# Control_Board.net
KiCad netlist of a schematic drawn in EAGLE
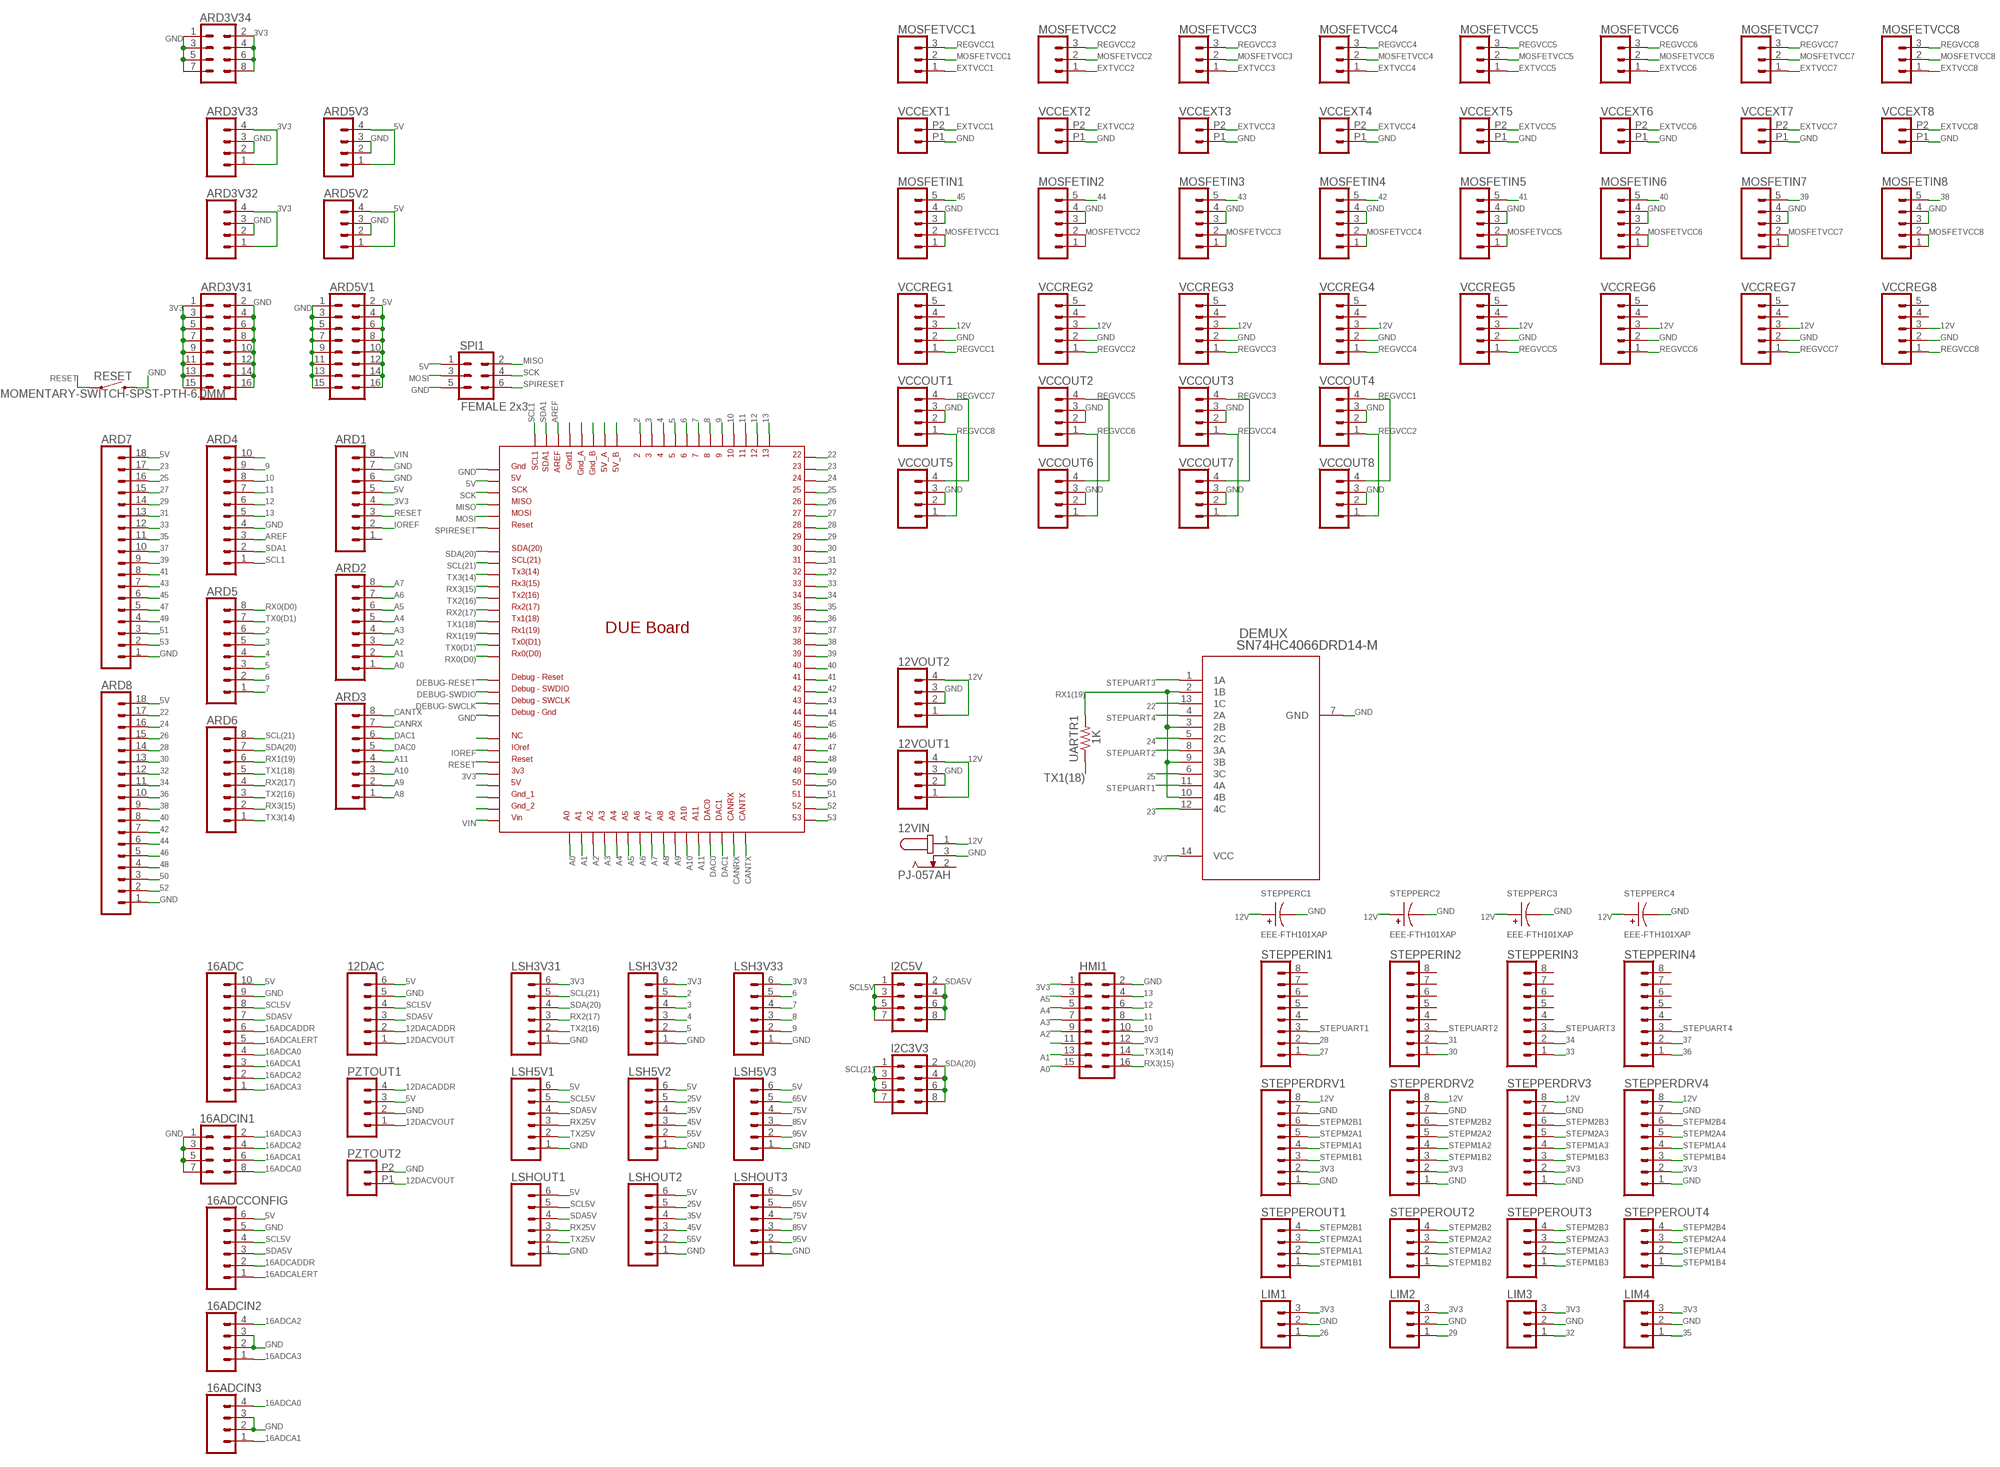
[diagram p0: schematic, sheet 1]

(export (version "E")
  (design (tool "Eeschema 10.0.6"))
  (components
    (comp (ref "12DAC")
      (value "CONN_06LOCK")
      (footprint "eagle-import:1X06_LOCK")
      (libsource (lib "eagle-import") (part "CONN_06LOCK"))
    )
    (comp (ref "12VIN")
      (value "PJ-057AH")
      (footprint "eagle-import:CUI_PJ-057AH")
      (fields (field (name "DIGI-KEY_PART_NUMBER") "CP-057AH-ND") (field (name "MF") "CUI Inc."))
      (libsource (lib "eagle-import") (part "PJ-057AH"))
    )
    (comp (ref "12VOUT1")
      (value "CONN_04POLAR")
      (footprint "eagle-import:MOLEX-1X4")
      (libsource (lib "eagle-import") (part "CONN_04POLAR"))
    )
    (comp (ref "12VOUT2")
      (value "CONN_04POLAR")
      (footprint "eagle-import:MOLEX-1X4")
      (libsource (lib "eagle-import") (part "CONN_04POLAR"))
    )
    (comp (ref "16ADC")
      (value "CONN_10LOCK")
      (footprint "eagle-import:1X10_LOCK")
      (libsource (lib "eagle-import") (part "CONN_10LOCK"))
    )
    (comp (ref "16ADCCONFIG")
      (value "CONN_06LOCK")
      (footprint "eagle-import:1X06_LOCK")
      (libsource (lib "eagle-import") (part "CONN_06LOCK"))
    )
    (comp (ref "16ADCIN1")
      (value "CONN_04X2")
      (footprint "eagle-import:2X4")
      (libsource (lib "eagle-import") (part "CONN_04X2"))
    )
    (comp (ref "16ADCIN2")
      (value "CONN_04POLAR")
      (footprint "eagle-import:MOLEX-1X4")
      (libsource (lib "eagle-import") (part "CONN_04POLAR"))
    )
    (comp (ref "16ADCIN3")
      (value "CONN_04POLAR")
      (footprint "eagle-import:MOLEX-1X4")
      (libsource (lib "eagle-import") (part "CONN_04POLAR"))
    )
    (comp (ref "ARD1")
      (value "CONN_08LOCK")
      (footprint "eagle-import:1X08_LOCK")
      (libsource (lib "eagle-import") (part "CONN_08LOCK"))
    )
    (comp (ref "ARD2")
      (value "CONN_08LOCK")
      (footprint "eagle-import:1X08_LOCK")
      (libsource (lib "eagle-import") (part "CONN_08LOCK"))
    )
    (comp (ref "ARD3")
      (value "CONN_08LOCK")
      (footprint "eagle-import:1X08_LOCK")
      (libsource (lib "eagle-import") (part "CONN_08LOCK"))
    )
    (comp (ref "ARD3V31")
      (value "CONN_08X2")
      (footprint "eagle-import:2X8")
      (libsource (lib "eagle-import") (part "CONN_08X2"))
    )
    (comp (ref "ARD3V32")
      (value "CONN_04POLAR")
      (footprint "eagle-import:MOLEX-1X4")
      (libsource (lib "eagle-import") (part "CONN_04POLAR"))
    )
    (comp (ref "ARD3V33")
      (value "CONN_04POLAR")
      (footprint "eagle-import:MOLEX-1X4")
      (libsource (lib "eagle-import") (part "CONN_04POLAR"))
    )
    (comp (ref "ARD3V34")
      (value "CONN_04X2")
      (footprint "eagle-import:2X4")
      (libsource (lib "eagle-import") (part "CONN_04X2"))
    )
    (comp (ref "ARD4")
      (value "CONN_10LOCK")
      (footprint "eagle-import:1X10_LOCK")
      (libsource (lib "eagle-import") (part "CONN_10LOCK"))
    )
    (comp (ref "ARD5")
      (value "CONN_08LOCK")
      (footprint "eagle-import:1X08_LOCK")
      (libsource (lib "eagle-import") (part "CONN_08LOCK"))
    )
    (comp (ref "ARD5V1")
      (value "CONN_08X2")
      (footprint "eagle-import:2X8")
      (libsource (lib "eagle-import") (part "CONN_08X2"))
    )
    (comp (ref "ARD5V2")
      (value "CONN_04POLAR")
      (footprint "eagle-import:MOLEX-1X4")
      (libsource (lib "eagle-import") (part "CONN_04POLAR"))
    )
    (comp (ref "ARD5V3")
      (value "CONN_04POLAR")
      (footprint "eagle-import:MOLEX-1X4")
      (libsource (lib "eagle-import") (part "CONN_04POLAR"))
    )
    (comp (ref "ARD6")
      (value "CONN_08LOCK")
      (footprint "eagle-import:1X08_LOCK")
      (libsource (lib "eagle-import") (part "CONN_08LOCK"))
    )
    (comp (ref "ARD7")
      (value "CONN_18")
      (footprint "eagle-import:1X18")
      (libsource (lib "eagle-import") (part "CONN_18"))
    )
    (comp (ref "ARD8")
      (value "CONN_18")
      (footprint "eagle-import:1X18")
      (libsource (lib "eagle-import") (part "CONN_18"))
    )
    (comp (ref "DEMUX")
      (value "SN74HC4066DRD14-M")
      (footprint "eagle-import:D14-M")
      (fields (field (name "MANUFACTURER_PART_NUMBER") "SN74HC4066DR"))
      (libsource (lib "eagle-import") (part "SN74HC4066DRD14-M"))
    )
    (comp (ref "HMI1")
      (value "CONN_08X2")
      (footprint "eagle-import:2X8")
      (libsource (lib "eagle-import") (part "CONN_08X2"))
    )
    (comp (ref "I2C3V3")
      (value "CONN_04X2")
      (footprint "eagle-import:2X4")
      (libsource (lib "eagle-import") (part "CONN_04X2"))
    )
    (comp (ref "I2C5V")
      (value "CONN_04X2")
      (footprint "eagle-import:2X4")
      (libsource (lib "eagle-import") (part "CONN_04X2"))
    )
    (comp (ref "LIM1")
      (value "CONN_03LOCK")
      (footprint "eagle-import:1X03_LOCK")
      (libsource (lib "eagle-import") (part "CONN_03LOCK"))
    )
    (comp (ref "LIM2")
      (value "CONN_03LOCK")
      (footprint "eagle-import:1X03_LOCK")
      (libsource (lib "eagle-import") (part "CONN_03LOCK"))
    )
    (comp (ref "LIM3")
      (value "CONN_03LOCK")
      (footprint "eagle-import:1X03_LOCK")
      (libsource (lib "eagle-import") (part "CONN_03LOCK"))
    )
    (comp (ref "LIM4")
      (value "CONN_03LOCK")
      (footprint "eagle-import:1X03_LOCK")
      (libsource (lib "eagle-import") (part "CONN_03LOCK"))
    )
    (comp (ref "LSH3V31")
      (value "CONN_06NO_SILK_FEMALE_PTH")
      (footprint "eagle-import:1X06_NO_SILK")
      (libsource (lib "eagle-import") (part "CONN_06NO_SILK_FEMALE_PTH"))
    )
    (comp (ref "LSH3V32")
      (value "CONN_06NO_SILK_FEMALE_PTH")
      (footprint "eagle-import:1X06_NO_SILK")
      (libsource (lib "eagle-import") (part "CONN_06NO_SILK_FEMALE_PTH"))
    )
    (comp (ref "LSH3V33")
      (value "CONN_06NO_SILK_FEMALE_PTH")
      (footprint "eagle-import:1X06_NO_SILK")
      (libsource (lib "eagle-import") (part "CONN_06NO_SILK_FEMALE_PTH"))
    )
    (comp (ref "LSH5V1")
      (value "CONN_06NO_SILK_FEMALE_PTH")
      (footprint "eagle-import:1X06_NO_SILK")
      (libsource (lib "eagle-import") (part "CONN_06NO_SILK_FEMALE_PTH"))
    )
    (comp (ref "LSH5V2")
      (value "CONN_06NO_SILK_FEMALE_PTH")
      (footprint "eagle-import:1X06_NO_SILK")
      (libsource (lib "eagle-import") (part "CONN_06NO_SILK_FEMALE_PTH"))
    )
    (comp (ref "LSH5V3")
      (value "CONN_06NO_SILK_FEMALE_PTH")
      (footprint "eagle-import:1X06_NO_SILK")
      (libsource (lib "eagle-import") (part "CONN_06NO_SILK_FEMALE_PTH"))
    )
    (comp (ref "LSHOUT1")
      (value "CONN_06LOCK")
      (footprint "eagle-import:1X06_LOCK")
      (libsource (lib "eagle-import") (part "CONN_06LOCK"))
    )
    (comp (ref "LSHOUT2")
      (value "CONN_06LOCK")
      (footprint "eagle-import:1X06_LOCK")
      (libsource (lib "eagle-import") (part "CONN_06LOCK"))
    )
    (comp (ref "LSHOUT3")
      (value "CONN_06LOCK")
      (footprint "eagle-import:1X06_LOCK")
      (libsource (lib "eagle-import") (part "CONN_06LOCK"))
    )
    (comp (ref "MOSFETIN1")
      (value "CONN_05LOCK")
      (footprint "eagle-import:1X05_LOCK")
      (libsource (lib "eagle-import") (part "CONN_05LOCK"))
    )
    (comp (ref "MOSFETIN2")
      (value "CONN_05LOCK")
      (footprint "eagle-import:1X05_LOCK")
      (libsource (lib "eagle-import") (part "CONN_05LOCK"))
    )
    (comp (ref "MOSFETIN3")
      (value "CONN_05LOCK")
      (footprint "eagle-import:1X05_LOCK")
      (libsource (lib "eagle-import") (part "CONN_05LOCK"))
    )
    (comp (ref "MOSFETIN4")
      (value "CONN_05LOCK")
      (footprint "eagle-import:1X05_LOCK")
      (libsource (lib "eagle-import") (part "CONN_05LOCK"))
    )
    (comp (ref "MOSFETIN5")
      (value "CONN_05LOCK")
      (footprint "eagle-import:1X05_LOCK")
      (libsource (lib "eagle-import") (part "CONN_05LOCK"))
    )
    (comp (ref "MOSFETIN6")
      (value "CONN_05LOCK")
      (footprint "eagle-import:1X05_LOCK")
      (libsource (lib "eagle-import") (part "CONN_05LOCK"))
    )
    (comp (ref "MOSFETIN7")
      (value "CONN_05LOCK")
      (footprint "eagle-import:1X05_LOCK")
      (libsource (lib "eagle-import") (part "CONN_05LOCK"))
    )
    (comp (ref "MOSFETIN8")
      (value "CONN_05LOCK")
      (footprint "eagle-import:1X05_LOCK")
      (libsource (lib "eagle-import") (part "CONN_05LOCK"))
    )
    (comp (ref "MOSFETVCC1")
      (value "CONN_03LOCK")
      (footprint "eagle-import:1X03_LOCK")
      (libsource (lib "eagle-import") (part "CONN_03LOCK"))
    )
    (comp (ref "MOSFETVCC2")
      (value "CONN_03LOCK")
      (footprint "eagle-import:1X03_LOCK")
      (libsource (lib "eagle-import") (part "CONN_03LOCK"))
    )
    (comp (ref "MOSFETVCC3")
      (value "CONN_03LOCK")
      (footprint "eagle-import:1X03_LOCK")
      (libsource (lib "eagle-import") (part "CONN_03LOCK"))
    )
    (comp (ref "MOSFETVCC4")
      (value "CONN_03LOCK")
      (footprint "eagle-import:1X03_LOCK")
      (libsource (lib "eagle-import") (part "CONN_03LOCK"))
    )
    (comp (ref "MOSFETVCC5")
      (value "CONN_03LOCK")
      (footprint "eagle-import:1X03_LOCK")
      (libsource (lib "eagle-import") (part "CONN_03LOCK"))
    )
    (comp (ref "MOSFETVCC6")
      (value "CONN_03LOCK")
      (footprint "eagle-import:1X03_LOCK")
      (libsource (lib "eagle-import") (part "CONN_03LOCK"))
    )
    (comp (ref "MOSFETVCC7")
      (value "CONN_03LOCK")
      (footprint "eagle-import:1X03_LOCK")
      (libsource (lib "eagle-import") (part "CONN_03LOCK"))
    )
    (comp (ref "MOSFETVCC8")
      (value "CONN_03LOCK")
      (footprint "eagle-import:1X03_LOCK")
      (libsource (lib "eagle-import") (part "CONN_03LOCK"))
    )
    (comp (ref "PZTOUT1")
      (value "CONN_04LOCK")
      (footprint "eagle-import:1X04_LOCK")
      (libsource (lib "eagle-import") (part "CONN_04LOCK"))
    )
    (comp (ref "PZTOUT2")
      (value "CONN_022.54MM_SCREWTERM")
      (footprint "eagle-import:1X02_2.54_SCREWTERM")
      (libsource (lib "eagle-import") (part "CONN_022.54MM_SCREWTERM"))
    )
    (comp (ref "RESET")
      (value "MOMENTARY-SWITCH-SPST-PTH-6.0MM")
      (footprint "eagle-import:TACTILE_SWITCH_PTH_6.0MM")
      (libsource (lib "eagle-import") (part "MOMENTARY-SWITCH-SPST-PTH-6.0MM"))
    )
    (comp (ref "SPI1")
      (value "FEMALE 2x3")
      (footprint "eagle-import:2X3")
      (libsource (lib "eagle-import") (part "CONN_03X2FEMALE"))
    )
    (comp (ref "STEPPERC1")
      (value "EEE-FTH101XAP")
      (footprint "eagle-import:CAPAE660X800N")
      (fields (field (name "DIGI-KEY_PART_NUMBER") "PCE5024CT-ND") (field (name "MF") "Panasonic Electronic"))
      (libsource (lib "eagle-import") (part "EEE-FTH101XAP"))
    )
    (comp (ref "STEPPERC2")
      (value "EEE-FTH101XAP")
      (footprint "eagle-import:CAPAE660X800N")
      (fields (field (name "DIGI-KEY_PART_NUMBER") "PCE5024CT-ND") (field (name "MF") "Panasonic Electronic"))
      (libsource (lib "eagle-import") (part "EEE-FTH101XAP"))
    )
    (comp (ref "STEPPERC3")
      (value "EEE-FTH101XAP")
      (footprint "eagle-import:CAPAE660X800N")
      (fields (field (name "DIGI-KEY_PART_NUMBER") "PCE5024CT-ND") (field (name "MF") "Panasonic Electronic"))
      (libsource (lib "eagle-import") (part "EEE-FTH101XAP"))
    )
    (comp (ref "STEPPERC4")
      (value "EEE-FTH101XAP")
      (footprint "eagle-import:CAPAE660X800N")
      (fields (field (name "DIGI-KEY_PART_NUMBER") "PCE5024CT-ND") (field (name "MF") "Panasonic Electronic"))
      (libsource (lib "eagle-import") (part "EEE-FTH101XAP"))
    )
    (comp (ref "STEPPERDRV1")
      (value "CONN_08NO_SILK_FEMALE_PTH")
      (footprint "eagle-import:1X08_NO_SILK")
      (libsource (lib "eagle-import") (part "CONN_08NO_SILK_FEMALE_PTH"))
    )
    (comp (ref "STEPPERDRV2")
      (value "CONN_08NO_SILK_FEMALE_PTH")
      (footprint "eagle-import:1X08_NO_SILK")
      (libsource (lib "eagle-import") (part "CONN_08NO_SILK_FEMALE_PTH"))
    )
    (comp (ref "STEPPERDRV3")
      (value "CONN_08NO_SILK_FEMALE_PTH")
      (footprint "eagle-import:1X08_NO_SILK")
      (libsource (lib "eagle-import") (part "CONN_08NO_SILK_FEMALE_PTH"))
    )
    (comp (ref "STEPPERDRV4")
      (value "CONN_08NO_SILK_FEMALE_PTH")
      (footprint "eagle-import:1X08_NO_SILK")
      (libsource (lib "eagle-import") (part "CONN_08NO_SILK_FEMALE_PTH"))
    )
    (comp (ref "STEPPERIN1")
      (value "CONN_08NO_SILK_FEMALE_PTH")
      (footprint "eagle-import:1X08_NO_SILK")
      (libsource (lib "eagle-import") (part "CONN_08NO_SILK_FEMALE_PTH"))
    )
    (comp (ref "STEPPERIN2")
      (value "CONN_08NO_SILK_FEMALE_PTH")
      (footprint "eagle-import:1X08_NO_SILK")
      (libsource (lib "eagle-import") (part "CONN_08NO_SILK_FEMALE_PTH"))
    )
    (comp (ref "STEPPERIN3")
      (value "CONN_08NO_SILK_FEMALE_PTH")
      (footprint "eagle-import:1X08_NO_SILK")
      (libsource (lib "eagle-import") (part "CONN_08NO_SILK_FEMALE_PTH"))
    )
    (comp (ref "STEPPERIN4")
      (value "CONN_08NO_SILK_FEMALE_PTH")
      (footprint "eagle-import:1X08_NO_SILK")
      (libsource (lib "eagle-import") (part "CONN_08NO_SILK_FEMALE_PTH"))
    )
    (comp (ref "STEPPEROUT1")
      (value "CONN_04POLAR")
      (footprint "eagle-import:MOLEX-1X4")
      (libsource (lib "eagle-import") (part "CONN_04POLAR"))
    )
    (comp (ref "STEPPEROUT2")
      (value "CONN_04POLAR")
      (footprint "eagle-import:MOLEX-1X4")
      (libsource (lib "eagle-import") (part "CONN_04POLAR"))
    )
    (comp (ref "STEPPEROUT3")
      (value "CONN_04POLAR")
      (footprint "eagle-import:MOLEX-1X4")
      (libsource (lib "eagle-import") (part "CONN_04POLAR"))
    )
    (comp (ref "STEPPEROUT4")
      (value "CONN_04POLAR")
      (footprint "eagle-import:MOLEX-1X4")
      (libsource (lib "eagle-import") (part "CONN_04POLAR"))
    )
    (comp (ref "U$1")
      (value "DUE-UPSIDEDOWN")
      (footprint "eagle-import:DUE-UPSIDEDOWN")
      (libsource (lib "eagle-import") (part "DUE-UPSIDEDOWN"))
    )
    (comp (ref "UARTR1")
      (value "1K")
      (footprint "eagle-import:0805")
      (libsource (lib "eagle-import") (part "RESISTOR0805"))
    )
    (comp (ref "VCCEXT1")
      (value "CONN_022.54MM_SCREWTERM")
      (footprint "eagle-import:1X02_2.54_SCREWTERM")
      (libsource (lib "eagle-import") (part "CONN_022.54MM_SCREWTERM"))
    )
    (comp (ref "VCCEXT2")
      (value "CONN_022.54MM_SCREWTERM")
      (footprint "eagle-import:1X02_2.54_SCREWTERM")
      (libsource (lib "eagle-import") (part "CONN_022.54MM_SCREWTERM"))
    )
    (comp (ref "VCCEXT3")
      (value "CONN_022.54MM_SCREWTERM")
      (footprint "eagle-import:1X02_2.54_SCREWTERM")
      (libsource (lib "eagle-import") (part "CONN_022.54MM_SCREWTERM"))
    )
    (comp (ref "VCCEXT4")
      (value "CONN_022.54MM_SCREWTERM")
      (footprint "eagle-import:1X02_2.54_SCREWTERM")
      (libsource (lib "eagle-import") (part "CONN_022.54MM_SCREWTERM"))
    )
    (comp (ref "VCCEXT5")
      (value "CONN_022.54MM_SCREWTERM")
      (footprint "eagle-import:1X02_2.54_SCREWTERM")
      (libsource (lib "eagle-import") (part "CONN_022.54MM_SCREWTERM"))
    )
    (comp (ref "VCCEXT6")
      (value "CONN_022.54MM_SCREWTERM")
      (footprint "eagle-import:1X02_2.54_SCREWTERM")
      (libsource (lib "eagle-import") (part "CONN_022.54MM_SCREWTERM"))
    )
    (comp (ref "VCCEXT7")
      (value "CONN_022.54MM_SCREWTERM")
      (footprint "eagle-import:1X02_2.54_SCREWTERM")
      (libsource (lib "eagle-import") (part "CONN_022.54MM_SCREWTERM"))
    )
    (comp (ref "VCCEXT8")
      (value "CONN_022.54MM_SCREWTERM")
      (footprint "eagle-import:1X02_2.54_SCREWTERM")
      (libsource (lib "eagle-import") (part "CONN_022.54MM_SCREWTERM"))
    )
    (comp (ref "VCCOUT1")
      (value "CONN_04LOCK")
      (footprint "eagle-import:1X04_LOCK")
      (libsource (lib "eagle-import") (part "CONN_04LOCK"))
    )
    (comp (ref "VCCOUT2")
      (value "CONN_04LOCK")
      (footprint "eagle-import:1X04_LOCK")
      (libsource (lib "eagle-import") (part "CONN_04LOCK"))
    )
    (comp (ref "VCCOUT3")
      (value "CONN_04LOCK")
      (footprint "eagle-import:1X04_LOCK")
      (libsource (lib "eagle-import") (part "CONN_04LOCK"))
    )
    (comp (ref "VCCOUT4")
      (value "CONN_04LOCK")
      (footprint "eagle-import:1X04_LOCK")
      (libsource (lib "eagle-import") (part "CONN_04LOCK"))
    )
    (comp (ref "VCCOUT5")
      (value "CONN_04POLAR")
      (footprint "eagle-import:MOLEX-1X4")
      (libsource (lib "eagle-import") (part "CONN_04POLAR"))
    )
    (comp (ref "VCCOUT6")
      (value "CONN_04POLAR")
      (footprint "eagle-import:MOLEX-1X4")
      (libsource (lib "eagle-import") (part "CONN_04POLAR"))
    )
    (comp (ref "VCCOUT7")
      (value "CONN_04POLAR")
      (footprint "eagle-import:MOLEX-1X4")
      (libsource (lib "eagle-import") (part "CONN_04POLAR"))
    )
    (comp (ref "VCCOUT8")
      (value "CONN_04POLAR")
      (footprint "eagle-import:MOLEX-1X4")
      (libsource (lib "eagle-import") (part "CONN_04POLAR"))
    )
    (comp (ref "VCCREG1")
      (value "CONN_05LOCK")
      (footprint "eagle-import:1X05_LOCK")
      (libsource (lib "eagle-import") (part "CONN_05LOCK"))
    )
    (comp (ref "VCCREG2")
      (value "CONN_05LOCK")
      (footprint "eagle-import:1X05_LOCK")
      (libsource (lib "eagle-import") (part "CONN_05LOCK"))
    )
    (comp (ref "VCCREG3")
      (value "CONN_05LOCK")
      (footprint "eagle-import:1X05_LOCK")
      (libsource (lib "eagle-import") (part "CONN_05LOCK"))
    )
    (comp (ref "VCCREG4")
      (value "CONN_05LOCK")
      (footprint "eagle-import:1X05_LOCK")
      (libsource (lib "eagle-import") (part "CONN_05LOCK"))
    )
    (comp (ref "VCCREG5")
      (value "CONN_05LOCK")
      (footprint "eagle-import:1X05_LOCK")
      (libsource (lib "eagle-import") (part "CONN_05LOCK"))
    )
    (comp (ref "VCCREG6")
      (value "CONN_05LOCK")
      (footprint "eagle-import:1X05_LOCK")
      (libsource (lib "eagle-import") (part "CONN_05LOCK"))
    )
    (comp (ref "VCCREG7")
      (value "CONN_05LOCK")
      (footprint "eagle-import:1X05_LOCK")
      (libsource (lib "eagle-import") (part "CONN_05LOCK"))
    )
    (comp (ref "VCCREG8")
      (value "CONN_05LOCK")
      (footprint "eagle-import:1X05_LOCK")
      (libsource (lib "eagle-import") (part "CONN_05LOCK"))
    )
  )
  (nets
    (net (code "1") (name "/2") (class "Default")
      (node (ref "ARD5") (pin "6") (pinfunction "6_6") (pintype "passive"))
      (node (ref "LSH3V32") (pin "5") (pinfunction "5_5") (pintype "passive"))
      (node (ref "U$1") (pin "2") (pinfunction "2_2") (pintype "bidirectional"))
    )
    (net (code "2") (name "/3") (class "Default")
      (node (ref "ARD5") (pin "5") (pinfunction "5_5") (pintype "passive"))
      (node (ref "LSH3V32") (pin "4") (pinfunction "4_4") (pintype "passive"))
      (node (ref "U$1") (pin "3") (pinfunction "3_3") (pintype "bidirectional"))
    )
    (net (code "3") (name "/3V3") (class "Default")
      (node (ref "ARD1") (pin "4") (pinfunction "4_4") (pintype "passive"))
      (node (ref "ARD3V31") (pin "1") (pinfunction "1_1") (pintype "passive"))
      (node (ref "ARD3V31") (pin "11") (pinfunction "11_11") (pintype "passive"))
      (node (ref "ARD3V31") (pin "13") (pinfunction "13_13") (pintype "passive"))
      (node (ref "ARD3V31") (pin "15") (pinfunction "15_15") (pintype "passive"))
      (node (ref "ARD3V31") (pin "3") (pinfunction "3_3") (pintype "passive"))
      (node (ref "ARD3V31") (pin "5") (pinfunction "5_5") (pintype "passive"))
      (node (ref "ARD3V31") (pin "7") (pinfunction "7_7") (pintype "passive"))
      (node (ref "ARD3V31") (pin "9") (pinfunction "9_9") (pintype "passive"))
      (node (ref "ARD3V32") (pin "1") (pinfunction "1_1") (pintype "passive"))
      (node (ref "ARD3V32") (pin "4") (pinfunction "4_4") (pintype "passive"))
      (node (ref "ARD3V33") (pin "1") (pinfunction "1_1") (pintype "passive"))
      (node (ref "ARD3V33") (pin "4") (pinfunction "4_4") (pintype "passive"))
      (node (ref "ARD3V34") (pin "2") (pinfunction "2_2") (pintype "passive"))
      (node (ref "ARD3V34") (pin "4") (pinfunction "4_4") (pintype "passive"))
      (node (ref "ARD3V34") (pin "6") (pinfunction "6_6") (pintype "passive"))
      (node (ref "ARD3V34") (pin "8") (pinfunction "8_8") (pintype "passive"))
      (node (ref "DEMUX") (pin "14") (pinfunction "VCC_14") (pintype "power_in"))
      (node (ref "HMI1") (pin "1") (pinfunction "1_1") (pintype "passive"))
      (node (ref "HMI1") (pin "12") (pinfunction "12_12") (pintype "passive"))
      (node (ref "LIM1") (pin "3") (pinfunction "3_3") (pintype "passive"))
      (node (ref "LIM2") (pin "3") (pinfunction "3_3") (pintype "passive"))
      (node (ref "LIM3") (pin "3") (pinfunction "3_3") (pintype "passive"))
      (node (ref "LIM4") (pin "3") (pinfunction "3_3") (pintype "passive"))
      (node (ref "LSH3V31") (pin "6") (pinfunction "6_6") (pintype "passive"))
      (node (ref "LSH3V32") (pin "6") (pinfunction "6_6") (pintype "passive"))
      (node (ref "LSH3V33") (pin "6") (pinfunction "6_6") (pintype "passive"))
      (node (ref "STEPPERDRV1") (pin "2") (pinfunction "2_2") (pintype "passive"))
      (node (ref "STEPPERDRV2") (pin "2") (pinfunction "2_2") (pintype "passive"))
      (node (ref "STEPPERDRV3") (pin "2") (pinfunction "2_2") (pintype "passive"))
      (node (ref "STEPPERDRV4") (pin "2") (pinfunction "2_2") (pintype "passive"))
      (node (ref "U$1") (pin "3V3") (pinfunction "3V3_3V3") (pintype "bidirectional"))
    )
    (net (code "4") (name "/4") (class "Default")
      (node (ref "ARD5") (pin "4") (pinfunction "4_4") (pintype "passive"))
      (node (ref "LSH3V32") (pin "3") (pinfunction "3_3") (pintype "passive"))
      (node (ref "U$1") (pin "4") (pinfunction "4_4") (pintype "bidirectional"))
    )
    (net (code "5") (name "/5") (class "Default")
      (node (ref "ARD5") (pin "3") (pinfunction "3_3") (pintype "passive"))
      (node (ref "LSH3V32") (pin "2") (pinfunction "2_2") (pintype "passive"))
      (node (ref "U$1") (pin "5") (pinfunction "5_5") (pintype "bidirectional"))
    )
    (net (code "6") (name "/5V") (class "Default")
      (node (ref "12DAC") (pin "6") (pinfunction "6_6") (pintype "passive"))
      (node (ref "16ADC") (pin "10") (pinfunction "10_10") (pintype "passive"))
      (node (ref "16ADCCONFIG") (pin "6") (pinfunction "6_6") (pintype "passive"))
      (node (ref "ARD1") (pin "5") (pinfunction "5_5") (pintype "passive"))
      (node (ref "ARD5V1") (pin "10") (pinfunction "10_10") (pintype "passive"))
      (node (ref "ARD5V1") (pin "12") (pinfunction "12_12") (pintype "passive"))
      (node (ref "ARD5V1") (pin "14") (pinfunction "14_14") (pintype "passive"))
      (node (ref "ARD5V1") (pin "16") (pinfunction "16_16") (pintype "passive"))
      (node (ref "ARD5V1") (pin "2") (pinfunction "2_2") (pintype "passive"))
      (node (ref "ARD5V1") (pin "4") (pinfunction "4_4") (pintype "passive"))
      (node (ref "ARD5V1") (pin "6") (pinfunction "6_6") (pintype "passive"))
      (node (ref "ARD5V1") (pin "8") (pinfunction "8_8") (pintype "passive"))
      (node (ref "ARD5V2") (pin "1") (pinfunction "1_1") (pintype "passive"))
      (node (ref "ARD5V2") (pin "4") (pinfunction "4_4") (pintype "passive"))
      (node (ref "ARD5V3") (pin "1") (pinfunction "1_1") (pintype "passive"))
      (node (ref "ARD5V3") (pin "4") (pinfunction "4_4") (pintype "passive"))
      (node (ref "ARD7") (pin "18") (pinfunction "18_18") (pintype "passive"))
      (node (ref "ARD8") (pin "18") (pinfunction "18_18") (pintype "passive"))
      (node (ref "LSH5V1") (pin "6") (pinfunction "6_6") (pintype "passive"))
      (node (ref "LSH5V2") (pin "6") (pinfunction "6_6") (pintype "passive"))
      (node (ref "LSH5V3") (pin "6") (pinfunction "6_6") (pintype "passive"))
      (node (ref "LSHOUT1") (pin "6") (pinfunction "6_6") (pintype "passive"))
      (node (ref "LSHOUT2") (pin "6") (pinfunction "6_6") (pintype "passive"))
      (node (ref "LSHOUT3") (pin "6") (pinfunction "6_6") (pintype "passive"))
      (node (ref "PZTOUT1") (pin "3") (pinfunction "3_3") (pintype "passive"))
      (node (ref "SPI1") (pin "1") (pinfunction "1_1") (pintype "bidirectional"))
      (node (ref "U$1") (pin "5V") (pinfunction "5V_5V") (pintype "bidirectional"))
      (node (ref "U$1") (pin "5V_A") (pinfunction "5V_A_5V_A") (pintype "bidirectional"))
      (node (ref "U$1") (pin "5V_B") (pinfunction "5V_B_5V_B") (pintype "bidirectional"))
      (node (ref "U$1") (pin "GND_ICSP") (pinfunction "GND_ICSP_GND_ICSP") (pintype "bidirectional"))
    )
    (net (code "7") (name "/6") (class "Default")
      (node (ref "ARD5") (pin "2") (pinfunction "2_2") (pintype "passive"))
      (node (ref "LSH3V33") (pin "5") (pinfunction "5_5") (pintype "passive"))
      (node (ref "U$1") (pin "6") (pinfunction "6_6") (pintype "bidirectional"))
    )
    (net (code "8") (name "/7") (class "Default")
      (node (ref "ARD5") (pin "1") (pinfunction "1_1") (pintype "passive"))
      (node (ref "LSH3V33") (pin "4") (pinfunction "4_4") (pintype "passive"))
      (node (ref "U$1") (pin "7") (pinfunction "7_7") (pintype "bidirectional"))
    )
    (net (code "9") (name "/8") (class "Default")
      (node (ref "ARD4") (pin "10") (pinfunction "10_10") (pintype "passive"))
      (node (ref "LSH3V33") (pin "3") (pinfunction "3_3") (pintype "passive"))
      (node (ref "U$1") (pin "8") (pinfunction "8_8") (pintype "bidirectional"))
    )
    (net (code "10") (name "/9") (class "Default")
      (node (ref "ARD4") (pin "9") (pinfunction "9_9") (pintype "passive"))
      (node (ref "LSH3V33") (pin "2") (pinfunction "2_2") (pintype "passive"))
      (node (ref "U$1") (pin "9") (pinfunction "9_9") (pintype "bidirectional"))
    )
    (net (code "11") (name "/10") (class "Default")
      (node (ref "ARD4") (pin "8") (pinfunction "8_8") (pintype "passive"))
      (node (ref "HMI1") (pin "10") (pinfunction "10_10") (pintype "passive"))
      (node (ref "U$1") (pin "10") (pinfunction "10_10") (pintype "bidirectional"))
    )
    (net (code "12") (name "/11") (class "Default")
      (node (ref "ARD4") (pin "7") (pinfunction "7_7") (pintype "passive"))
      (node (ref "HMI1") (pin "8") (pinfunction "8_8") (pintype "passive"))
      (node (ref "U$1") (pin "11") (pinfunction "11_11") (pintype "bidirectional"))
    )
    (net (code "13") (name "/12") (class "Default")
      (node (ref "ARD4") (pin "6") (pinfunction "6_6") (pintype "passive"))
      (node (ref "HMI1") (pin "6") (pinfunction "6_6") (pintype "passive"))
      (node (ref "U$1") (pin "12") (pinfunction "12_12") (pintype "bidirectional"))
    )
    (net (code "14") (name "/12DACADDR") (class "Default")
      (node (ref "12DAC") (pin "2") (pinfunction "2_2") (pintype "passive"))
      (node (ref "PZTOUT1") (pin "4") (pinfunction "4_4") (pintype "passive"))
    )
    (net (code "15") (name "/12DACVOUT") (class "Default")
      (node (ref "12DAC") (pin "1") (pinfunction "1_1") (pintype "passive"))
      (node (ref "PZTOUT1") (pin "1") (pinfunction "1_1") (pintype "passive"))
      (node (ref "PZTOUT2") (pin "P1") (pinfunction "1_P1") (pintype "passive"))
    )
    (net (code "16") (name "/12V") (class "Default")
      (node (ref "12VIN") (pin "1") (pinfunction "1_1") (pintype "passive"))
      (node (ref "12VOUT1") (pin "1") (pinfunction "1_1") (pintype "passive"))
      (node (ref "12VOUT1") (pin "4") (pinfunction "4_4") (pintype "passive"))
      (node (ref "12VOUT2") (pin "1") (pinfunction "1_1") (pintype "passive"))
      (node (ref "12VOUT2") (pin "4") (pinfunction "4_4") (pintype "passive"))
      (node (ref "STEPPERC1") (pin "1") (pinfunction "1_1") (pintype "passive"))
      (node (ref "STEPPERC2") (pin "1") (pinfunction "1_1") (pintype "passive"))
      (node (ref "STEPPERC3") (pin "1") (pinfunction "1_1") (pintype "passive"))
      (node (ref "STEPPERC4") (pin "1") (pinfunction "1_1") (pintype "passive"))
      (node (ref "STEPPERDRV1") (pin "8") (pinfunction "8_8") (pintype "passive"))
      (node (ref "STEPPERDRV2") (pin "8") (pinfunction "8_8") (pintype "passive"))
      (node (ref "STEPPERDRV3") (pin "8") (pinfunction "8_8") (pintype "passive"))
      (node (ref "STEPPERDRV4") (pin "8") (pinfunction "8_8") (pintype "passive"))
      (node (ref "VCCREG1") (pin "3") (pinfunction "3_3") (pintype "passive"))
      (node (ref "VCCREG2") (pin "3") (pinfunction "3_3") (pintype "passive"))
      (node (ref "VCCREG3") (pin "3") (pinfunction "3_3") (pintype "passive"))
      (node (ref "VCCREG4") (pin "3") (pinfunction "3_3") (pintype "passive"))
      (node (ref "VCCREG5") (pin "3") (pinfunction "3_3") (pintype "passive"))
      (node (ref "VCCREG6") (pin "3") (pinfunction "3_3") (pintype "passive"))
      (node (ref "VCCREG7") (pin "3") (pinfunction "3_3") (pintype "passive"))
      (node (ref "VCCREG8") (pin "3") (pinfunction "3_3") (pintype "passive"))
    )
    (net (code "17") (name "/13") (class "Default")
      (node (ref "ARD4") (pin "5") (pinfunction "5_5") (pintype "passive"))
      (node (ref "HMI1") (pin "4") (pinfunction "4_4") (pintype "passive"))
      (node (ref "U$1") (pin "13") (pinfunction "13_13") (pintype "bidirectional"))
    )
    (net (code "18") (name "/16ADCA0") (class "Default")
      (node (ref "16ADC") (pin "4") (pinfunction "4_4") (pintype "passive"))
      (node (ref "16ADCIN1") (pin "8") (pinfunction "8_8") (pintype "passive"))
      (node (ref "16ADCIN3") (pin "4") (pinfunction "4_4") (pintype "passive"))
    )
    (net (code "19") (name "/16ADCA1") (class "Default")
      (node (ref "16ADC") (pin "3") (pinfunction "3_3") (pintype "passive"))
      (node (ref "16ADCIN1") (pin "6") (pinfunction "6_6") (pintype "passive"))
      (node (ref "16ADCIN3") (pin "1") (pinfunction "1_1") (pintype "passive"))
    )
    (net (code "20") (name "/16ADCA2") (class "Default")
      (node (ref "16ADC") (pin "2") (pinfunction "2_2") (pintype "passive"))
      (node (ref "16ADCIN1") (pin "4") (pinfunction "4_4") (pintype "passive"))
      (node (ref "16ADCIN2") (pin "4") (pinfunction "4_4") (pintype "passive"))
    )
    (net (code "21") (name "/16ADCA3") (class "Default")
      (node (ref "16ADC") (pin "1") (pinfunction "1_1") (pintype "passive"))
      (node (ref "16ADCIN1") (pin "2") (pinfunction "2_2") (pintype "passive"))
      (node (ref "16ADCIN2") (pin "1") (pinfunction "1_1") (pintype "passive"))
    )
    (net (code "22") (name "/16ADCADDR") (class "Default")
      (node (ref "16ADC") (pin "6") (pinfunction "6_6") (pintype "passive"))
      (node (ref "16ADCCONFIG") (pin "2") (pinfunction "2_2") (pintype "passive"))
    )
    (net (code "23") (name "/16ADCALERT") (class "Default")
      (node (ref "16ADC") (pin "5") (pinfunction "5_5") (pintype "passive"))
      (node (ref "16ADCCONFIG") (pin "1") (pinfunction "1_1") (pintype "passive"))
    )
    (net (code "24") (name "/22") (class "Default")
      (node (ref "ARD8") (pin "17") (pinfunction "17_17") (pintype "passive"))
      (node (ref "DEMUX") (pin "13") (pinfunction "1C_13") (pintype "input"))
      (node (ref "U$1") (pin "22") (pinfunction "22_22") (pintype "bidirectional"))
    )
    (net (code "25") (name "/23") (class "Default")
      (node (ref "ARD7") (pin "17") (pinfunction "17_17") (pintype "passive"))
      (node (ref "DEMUX") (pin "12") (pinfunction "4C_12") (pintype "input"))
      (node (ref "U$1") (pin "23") (pinfunction "23_23") (pintype "bidirectional"))
    )
    (net (code "26") (name "/24") (class "Default")
      (node (ref "ARD8") (pin "16") (pinfunction "16_16") (pintype "passive"))
      (node (ref "DEMUX") (pin "5") (pinfunction "2C_5") (pintype "input"))
      (node (ref "U$1") (pin "24") (pinfunction "24_24") (pintype "bidirectional"))
    )
    (net (code "27") (name "/25") (class "Default")
      (node (ref "ARD7") (pin "16") (pinfunction "16_16") (pintype "passive"))
      (node (ref "DEMUX") (pin "6") (pinfunction "3C_6") (pintype "input"))
      (node (ref "U$1") (pin "25") (pinfunction "25_25") (pintype "bidirectional"))
    )
    (net (code "28") (name "/25V") (class "Default")
      (node (ref "LSH5V2") (pin "5") (pinfunction "5_5") (pintype "passive"))
      (node (ref "LSHOUT2") (pin "5") (pinfunction "5_5") (pintype "passive"))
    )
    (net (code "29") (name "/26") (class "Default")
      (node (ref "ARD8") (pin "15") (pinfunction "15_15") (pintype "passive"))
      (node (ref "LIM1") (pin "1") (pinfunction "1_1") (pintype "passive"))
      (node (ref "U$1") (pin "26") (pinfunction "26_26") (pintype "bidirectional"))
    )
    (net (code "30") (name "/27") (class "Default")
      (node (ref "ARD7") (pin "15") (pinfunction "15_15") (pintype "passive"))
      (node (ref "STEPPERIN1") (pin "1") (pinfunction "1_1") (pintype "passive"))
      (node (ref "U$1") (pin "27") (pinfunction "27_27") (pintype "bidirectional"))
    )
    (net (code "31") (name "/28") (class "Default")
      (node (ref "ARD8") (pin "14") (pinfunction "14_14") (pintype "passive"))
      (node (ref "STEPPERIN1") (pin "2") (pinfunction "2_2") (pintype "passive"))
      (node (ref "U$1") (pin "28") (pinfunction "28_28") (pintype "bidirectional"))
    )
    (net (code "32") (name "/29") (class "Default")
      (node (ref "ARD7") (pin "14") (pinfunction "14_14") (pintype "passive"))
      (node (ref "LIM2") (pin "1") (pinfunction "1_1") (pintype "passive"))
      (node (ref "U$1") (pin "29") (pinfunction "29_29") (pintype "bidirectional"))
    )
    (net (code "33") (name "/30") (class "Default")
      (node (ref "ARD8") (pin "13") (pinfunction "13_13") (pintype "passive"))
      (node (ref "STEPPERIN2") (pin "1") (pinfunction "1_1") (pintype "passive"))
      (node (ref "U$1") (pin "30") (pinfunction "30_30") (pintype "bidirectional"))
    )
    (net (code "34") (name "/31") (class "Default")
      (node (ref "ARD7") (pin "13") (pinfunction "13_13") (pintype "passive"))
      (node (ref "STEPPERIN2") (pin "2") (pinfunction "2_2") (pintype "passive"))
      (node (ref "U$1") (pin "31") (pinfunction "31_31") (pintype "bidirectional"))
    )
    (net (code "35") (name "/32") (class "Default")
      (node (ref "ARD8") (pin "12") (pinfunction "12_12") (pintype "passive"))
      (node (ref "LIM3") (pin "1") (pinfunction "1_1") (pintype "passive"))
      (node (ref "U$1") (pin "32") (pinfunction "32_32") (pintype "bidirectional"))
    )
    (net (code "36") (name "/33") (class "Default")
      (node (ref "ARD7") (pin "12") (pinfunction "12_12") (pintype "passive"))
      (node (ref "STEPPERIN3") (pin "1") (pinfunction "1_1") (pintype "passive"))
      (node (ref "U$1") (pin "33") (pinfunction "33_33") (pintype "bidirectional"))
    )
    (net (code "37") (name "/34") (class "Default")
      (node (ref "ARD8") (pin "11") (pinfunction "11_11") (pintype "passive"))
      (node (ref "STEPPERIN3") (pin "2") (pinfunction "2_2") (pintype "passive"))
      (node (ref "U$1") (pin "34") (pinfunction "34_34") (pintype "bidirectional"))
    )
    (net (code "38") (name "/35") (class "Default")
      (node (ref "ARD7") (pin "11") (pinfunction "11_11") (pintype "passive"))
      (node (ref "LIM4") (pin "1") (pinfunction "1_1") (pintype "passive"))
      (node (ref "U$1") (pin "35") (pinfunction "35_35") (pintype "bidirectional"))
    )
    (net (code "39") (name "/35V") (class "Default")
      (node (ref "LSH5V2") (pin "4") (pinfunction "4_4") (pintype "passive"))
      (node (ref "LSHOUT2") (pin "4") (pinfunction "4_4") (pintype "passive"))
    )
    (net (code "40") (name "/36") (class "Default")
      (node (ref "ARD8") (pin "10") (pinfunction "10_10") (pintype "passive"))
      (node (ref "STEPPERIN4") (pin "1") (pinfunction "1_1") (pintype "passive"))
      (node (ref "U$1") (pin "36") (pinfunction "36_36") (pintype "bidirectional"))
    )
    (net (code "41") (name "/37") (class "Default")
      (node (ref "ARD7") (pin "10") (pinfunction "10_10") (pintype "passive"))
      (node (ref "STEPPERIN4") (pin "2") (pinfunction "2_2") (pintype "passive"))
      (node (ref "U$1") (pin "37") (pinfunction "37_37") (pintype "bidirectional"))
    )
    (net (code "42") (name "/38") (class "Default")
      (node (ref "ARD8") (pin "9") (pinfunction "9_9") (pintype "passive"))
      (node (ref "MOSFETIN8") (pin "5") (pinfunction "5_5") (pintype "passive"))
      (node (ref "U$1") (pin "38") (pinfunction "38_38") (pintype "bidirectional"))
    )
    (net (code "43") (name "/39") (class "Default")
      (node (ref "ARD7") (pin "9") (pinfunction "9_9") (pintype "passive"))
      (node (ref "MOSFETIN7") (pin "5") (pinfunction "5_5") (pintype "passive"))
      (node (ref "U$1") (pin "39") (pinfunction "39_39") (pintype "bidirectional"))
    )
    (net (code "44") (name "/40") (class "Default")
      (node (ref "ARD8") (pin "8") (pinfunction "8_8") (pintype "passive"))
      (node (ref "MOSFETIN6") (pin "5") (pinfunction "5_5") (pintype "passive"))
      (node (ref "U$1") (pin "40") (pinfunction "40_40") (pintype "bidirectional"))
    )
    (net (code "45") (name "/41") (class "Default")
      (node (ref "ARD7") (pin "8") (pinfunction "8_8") (pintype "passive"))
      (node (ref "MOSFETIN5") (pin "5") (pinfunction "5_5") (pintype "passive"))
      (node (ref "U$1") (pin "41") (pinfunction "41_41") (pintype "bidirectional"))
    )
    (net (code "46") (name "/42") (class "Default")
      (node (ref "ARD8") (pin "7") (pinfunction "7_7") (pintype "passive"))
      (node (ref "MOSFETIN4") (pin "5") (pinfunction "5_5") (pintype "passive"))
      (node (ref "U$1") (pin "42") (pinfunction "42_42") (pintype "bidirectional"))
    )
    (net (code "47") (name "/43") (class "Default")
      (node (ref "ARD7") (pin "7") (pinfunction "7_7") (pintype "passive"))
      (node (ref "MOSFETIN3") (pin "5") (pinfunction "5_5") (pintype "passive"))
      (node (ref "U$1") (pin "43") (pinfunction "43_43") (pintype "bidirectional"))
    )
    (net (code "48") (name "/44") (class "Default")
      (node (ref "ARD8") (pin "6") (pinfunction "6_6") (pintype "passive"))
      (node (ref "MOSFETIN2") (pin "5") (pinfunction "5_5") (pintype "passive"))
      (node (ref "U$1") (pin "44") (pinfunction "44_44") (pintype "bidirectional"))
    )
    (net (code "49") (name "/45") (class "Default")
      (node (ref "ARD7") (pin "6") (pinfunction "6_6") (pintype "passive"))
      (node (ref "MOSFETIN1") (pin "5") (pinfunction "5_5") (pintype "passive"))
      (node (ref "U$1") (pin "45") (pinfunction "45_45") (pintype "bidirectional"))
    )
    (net (code "50") (name "/45V") (class "Default")
      (node (ref "LSH5V2") (pin "3") (pinfunction "3_3") (pintype "passive"))
      (node (ref "LSHOUT2") (pin "3") (pinfunction "3_3") (pintype "passive"))
    )
    (net (code "51") (name "/46") (class "Default")
      (node (ref "ARD8") (pin "5") (pinfunction "5_5") (pintype "passive"))
      (node (ref "U$1") (pin "46") (pinfunction "46_46") (pintype "bidirectional"))
    )
    (net (code "52") (name "/47") (class "Default")
      (node (ref "ARD7") (pin "5") (pinfunction "5_5") (pintype "passive"))
      (node (ref "U$1") (pin "47") (pinfunction "47_47") (pintype "bidirectional"))
    )
    (net (code "53") (name "/48") (class "Default")
      (node (ref "ARD8") (pin "4") (pinfunction "4_4") (pintype "passive"))
      (node (ref "U$1") (pin "48") (pinfunction "48_48") (pintype "bidirectional"))
    )
    (net (code "54") (name "/49") (class "Default")
      (node (ref "ARD7") (pin "4") (pinfunction "4_4") (pintype "passive"))
      (node (ref "U$1") (pin "49") (pinfunction "49_49") (pintype "bidirectional"))
    )
    (net (code "55") (name "/50") (class "Default")
      (node (ref "ARD8") (pin "3") (pinfunction "3_3") (pintype "passive"))
      (node (ref "U$1") (pin "50") (pinfunction "50_50") (pintype "bidirectional"))
    )
    (net (code "56") (name "/51") (class "Default")
      (node (ref "ARD7") (pin "3") (pinfunction "3_3") (pintype "passive"))
      (node (ref "U$1") (pin "51") (pinfunction "51_51") (pintype "bidirectional"))
    )
    (net (code "57") (name "/52") (class "Default")
      (node (ref "ARD8") (pin "2") (pinfunction "2_2") (pintype "passive"))
      (node (ref "U$1") (pin "52") (pinfunction "52_52") (pintype "bidirectional"))
    )
    (net (code "58") (name "/53") (class "Default")
      (node (ref "ARD7") (pin "2") (pinfunction "2_2") (pintype "passive"))
      (node (ref "U$1") (pin "53") (pinfunction "53_53") (pintype "bidirectional"))
    )
    (net (code "59") (name "/55V") (class "Default")
      (node (ref "LSH5V2") (pin "2") (pinfunction "2_2") (pintype "passive"))
      (node (ref "LSHOUT2") (pin "2") (pinfunction "2_2") (pintype "passive"))
    )
    (net (code "60") (name "/65V") (class "Default")
      (node (ref "LSH5V3") (pin "5") (pinfunction "5_5") (pintype "passive"))
      (node (ref "LSHOUT3") (pin "5") (pinfunction "5_5") (pintype "passive"))
    )
    (net (code "61") (name "/75V") (class "Default")
      (node (ref "LSH5V3") (pin "4") (pinfunction "4_4") (pintype "passive"))
      (node (ref "LSHOUT3") (pin "4") (pinfunction "4_4") (pintype "passive"))
    )
    (net (code "62") (name "/85V") (class "Default")
      (node (ref "LSH5V3") (pin "3") (pinfunction "3_3") (pintype "passive"))
      (node (ref "LSHOUT3") (pin "3") (pinfunction "3_3") (pintype "passive"))
    )
    (net (code "63") (name "/95V") (class "Default")
      (node (ref "LSH5V3") (pin "2") (pinfunction "2_2") (pintype "passive"))
      (node (ref "LSHOUT3") (pin "2") (pinfunction "2_2") (pintype "passive"))
    )
    (net (code "64") (name "/A0") (class "Default")
      (node (ref "ARD2") (pin "1") (pinfunction "1_1") (pintype "passive"))
      (node (ref "HMI1") (pin "15") (pinfunction "15_15") (pintype "passive"))
      (node (ref "U$1") (pin "A0") (pinfunction "A0_A0") (pintype "bidirectional"))
    )
    (net (code "65") (name "/A1") (class "Default")
      (node (ref "ARD2") (pin "2") (pinfunction "2_2") (pintype "passive"))
      (node (ref "HMI1") (pin "13") (pinfunction "13_13") (pintype "passive"))
      (node (ref "U$1") (pin "A1") (pinfunction "A1_A1") (pintype "bidirectional"))
    )
    (net (code "66") (name "/A2") (class "Default")
      (node (ref "ARD2") (pin "3") (pinfunction "3_3") (pintype "passive"))
      (node (ref "HMI1") (pin "9") (pinfunction "9_9") (pintype "passive"))
      (node (ref "U$1") (pin "A2") (pinfunction "A2_A2") (pintype "bidirectional"))
    )
    (net (code "67") (name "/A3") (class "Default")
      (node (ref "ARD2") (pin "4") (pinfunction "4_4") (pintype "passive"))
      (node (ref "HMI1") (pin "7") (pinfunction "7_7") (pintype "passive"))
      (node (ref "U$1") (pin "A3") (pinfunction "A3_A3") (pintype "bidirectional"))
    )
    (net (code "68") (name "/A4") (class "Default")
      (node (ref "ARD2") (pin "5") (pinfunction "5_5") (pintype "passive"))
      (node (ref "HMI1") (pin "5") (pinfunction "5_5") (pintype "passive"))
      (node (ref "U$1") (pin "A4") (pinfunction "A4_A4") (pintype "bidirectional"))
    )
    (net (code "69") (name "/A5") (class "Default")
      (node (ref "ARD2") (pin "6") (pinfunction "6_6") (pintype "passive"))
      (node (ref "HMI1") (pin "3") (pinfunction "3_3") (pintype "passive"))
      (node (ref "U$1") (pin "A5") (pinfunction "A5_A5") (pintype "bidirectional"))
    )
    (net (code "70") (name "/A6") (class "Default")
      (node (ref "ARD2") (pin "7") (pinfunction "7_7") (pintype "passive"))
      (node (ref "U$1") (pin "A6") (pinfunction "A6_A6") (pintype "bidirectional"))
    )
    (net (code "71") (name "/A7") (class "Default")
      (node (ref "ARD2") (pin "8") (pinfunction "8_8") (pintype "passive"))
      (node (ref "U$1") (pin "A7") (pinfunction "A7_A7") (pintype "bidirectional"))
    )
    (net (code "72") (name "/A8") (class "Default")
      (node (ref "ARD3") (pin "1") (pinfunction "1_1") (pintype "passive"))
      (node (ref "U$1") (pin "A8") (pinfunction "A8_A8") (pintype "bidirectional"))
    )
    (net (code "73") (name "/A9") (class "Default")
      (node (ref "ARD3") (pin "2") (pinfunction "2_2") (pintype "passive"))
      (node (ref "U$1") (pin "A9") (pinfunction "A9_A9") (pintype "bidirectional"))
    )
    (net (code "74") (name "/A10") (class "Default")
      (node (ref "ARD3") (pin "3") (pinfunction "3_3") (pintype "passive"))
      (node (ref "U$1") (pin "A10") (pinfunction "A10_A10") (pintype "bidirectional"))
    )
    (net (code "75") (name "/A11") (class "Default")
      (node (ref "ARD3") (pin "4") (pinfunction "4_4") (pintype "passive"))
      (node (ref "U$1") (pin "A11") (pinfunction "A11_A11") (pintype "bidirectional"))
    )
    (net (code "76") (name "/AREF") (class "Default")
      (node (ref "ARD4") (pin "3") (pinfunction "3_3") (pintype "passive"))
      (node (ref "U$1") (pin "AREF") (pinfunction "AREF_AREF") (pintype "bidirectional"))
      (node (ref "U$1") (pin "AREF1") (pinfunction "AREF_AREF1") (pintype "bidirectional"))
    )
    (net (code "77") (name "/CANRX") (class "Default")
      (node (ref "ARD3") (pin "7") (pinfunction "7_7") (pintype "passive"))
      (node (ref "U$1") (pin "CANRX") (pinfunction "CANRX_CANRX") (pintype "bidirectional"))
    )
    (net (code "78") (name "/CANTX") (class "Default")
      (node (ref "ARD3") (pin "8") (pinfunction "8_8") (pintype "passive"))
      (node (ref "U$1") (pin "CANTX") (pinfunction "CANTX_CANTX") (pintype "bidirectional"))
    )
    (net (code "79") (name "/DAC0") (class "Default")
      (node (ref "ARD3") (pin "5") (pinfunction "5_5") (pintype "passive"))
      (node (ref "U$1") (pin "DAC0") (pinfunction "DAC0_DAC0") (pintype "bidirectional"))
    )
    (net (code "80") (name "/DAC1") (class "Default")
      (node (ref "ARD3") (pin "6") (pinfunction "6_6") (pintype "passive"))
      (node (ref "U$1") (pin "DAC1") (pinfunction "DAC1_DAC1") (pintype "bidirectional"))
    )
    (net (code "81") (name "/DEBUG-RESET") (class "Default")
      (node (ref "U$1") (pin "RESET_DEBUG") (pinfunction "RESET_DEBUG_RESET_DEBUG") (pintype "bidirectional"))
    )
    (net (code "82") (name "/DEBUG-SWCLK") (class "Default")
      (node (ref "U$1") (pin "SWCLK_DEBUG") (pinfunction "SWCLK_DEBUG_SWCLK_DEBUG") (pintype "bidirectional"))
    )
    (net (code "83") (name "/DEBUG-SWDIO") (class "Default")
      (node (ref "U$1") (pin "SWDIO_DEBUG") (pinfunction "SWDIO_DEBUG_SWDIO_DEBUG") (pintype "bidirectional"))
    )
    (net (code "84") (name "/EXTVCC1") (class "Default")
      (node (ref "MOSFETVCC1") (pin "1") (pinfunction "1_1") (pintype "passive"))
      (node (ref "VCCEXT1") (pin "P2") (pinfunction "2_P2") (pintype "passive"))
    )
    (net (code "85") (name "/EXTVCC2") (class "Default")
      (node (ref "MOSFETVCC2") (pin "1") (pinfunction "1_1") (pintype "passive"))
      (node (ref "VCCEXT2") (pin "P2") (pinfunction "2_P2") (pintype "passive"))
    )
    (net (code "86") (name "/EXTVCC3") (class "Default")
      (node (ref "MOSFETVCC3") (pin "1") (pinfunction "1_1") (pintype "passive"))
      (node (ref "VCCEXT3") (pin "P2") (pinfunction "2_P2") (pintype "passive"))
    )
    (net (code "87") (name "/EXTVCC4") (class "Default")
      (node (ref "MOSFETVCC4") (pin "1") (pinfunction "1_1") (pintype "passive"))
      (node (ref "VCCEXT4") (pin "P2") (pinfunction "2_P2") (pintype "passive"))
    )
    (net (code "88") (name "/EXTVCC5") (class "Default")
      (node (ref "MOSFETVCC5") (pin "1") (pinfunction "1_1") (pintype "passive"))
      (node (ref "VCCEXT5") (pin "P2") (pinfunction "2_P2") (pintype "passive"))
    )
    (net (code "89") (name "/EXTVCC6") (class "Default")
      (node (ref "MOSFETVCC6") (pin "1") (pinfunction "1_1") (pintype "passive"))
      (node (ref "VCCEXT6") (pin "P2") (pinfunction "2_P2") (pintype "passive"))
    )
    (net (code "90") (name "/EXTVCC7") (class "Default")
      (node (ref "MOSFETVCC7") (pin "1") (pinfunction "1_1") (pintype "passive"))
      (node (ref "VCCEXT7") (pin "P2") (pinfunction "2_P2") (pintype "passive"))
    )
    (net (code "91") (name "/EXTVCC8") (class "Default")
      (node (ref "MOSFETVCC8") (pin "1") (pinfunction "1_1") (pintype "passive"))
      (node (ref "VCCEXT8") (pin "P2") (pinfunction "2_P2") (pintype "passive"))
    )
    (net (code "92") (name "/GND") (class "Default")
      (node (ref "12DAC") (pin "5") (pinfunction "5_5") (pintype "passive"))
      (node (ref "12VIN") (pin "3") (pinfunction "3_3") (pintype "passive"))
      (node (ref "12VOUT1") (pin "2") (pinfunction "2_2") (pintype "passive"))
      (node (ref "12VOUT1") (pin "3") (pinfunction "3_3") (pintype "passive"))
      (node (ref "12VOUT2") (pin "2") (pinfunction "2_2") (pintype "passive"))
      (node (ref "12VOUT2") (pin "3") (pinfunction "3_3") (pintype "passive"))
      (node (ref "16ADC") (pin "9") (pinfunction "9_9") (pintype "passive"))
      (node (ref "16ADCCONFIG") (pin "5") (pinfunction "5_5") (pintype "passive"))
      (node (ref "16ADCIN1") (pin "1") (pinfunction "1_1") (pintype "passive"))
      (node (ref "16ADCIN1") (pin "3") (pinfunction "3_3") (pintype "passive"))
      (node (ref "16ADCIN1") (pin "5") (pinfunction "5_5") (pintype "passive"))
      (node (ref "16ADCIN1") (pin "7") (pinfunction "7_7") (pintype "passive"))
      (node (ref "16ADCIN2") (pin "2") (pinfunction "2_2") (pintype "passive"))
      (node (ref "16ADCIN2") (pin "3") (pinfunction "3_3") (pintype "passive"))
      (node (ref "16ADCIN3") (pin "2") (pinfunction "2_2") (pintype "passive"))
      (node (ref "16ADCIN3") (pin "3") (pinfunction "3_3") (pintype "passive"))
      (node (ref "ARD1") (pin "6") (pinfunction "6_6") (pintype "passive"))
      (node (ref "ARD1") (pin "7") (pinfunction "7_7") (pintype "passive"))
      (node (ref "ARD3V31") (pin "10") (pinfunction "10_10") (pintype "passive"))
      (node (ref "ARD3V31") (pin "12") (pinfunction "12_12") (pintype "passive"))
      (node (ref "ARD3V31") (pin "14") (pinfunction "14_14") (pintype "passive"))
      (node (ref "ARD3V31") (pin "16") (pinfunction "16_16") (pintype "passive"))
      (node (ref "ARD3V31") (pin "2") (pinfunction "2_2") (pintype "passive"))
      (node (ref "ARD3V31") (pin "4") (pinfunction "4_4") (pintype "passive"))
      (node (ref "ARD3V31") (pin "6") (pinfunction "6_6") (pintype "passive"))
      (node (ref "ARD3V31") (pin "8") (pinfunction "8_8") (pintype "passive"))
      (node (ref "ARD3V32") (pin "2") (pinfunction "2_2") (pintype "passive"))
      (node (ref "ARD3V32") (pin "3") (pinfunction "3_3") (pintype "passive"))
      (node (ref "ARD3V33") (pin "2") (pinfunction "2_2") (pintype "passive"))
      (node (ref "ARD3V33") (pin "3") (pinfunction "3_3") (pintype "passive"))
      (node (ref "ARD3V34") (pin "1") (pinfunction "1_1") (pintype "passive"))
      (node (ref "ARD3V34") (pin "3") (pinfunction "3_3") (pintype "passive"))
      (node (ref "ARD3V34") (pin "5") (pinfunction "5_5") (pintype "passive"))
      (node (ref "ARD3V34") (pin "7") (pinfunction "7_7") (pintype "passive"))
      (node (ref "ARD4") (pin "4") (pinfunction "4_4") (pintype "passive"))
      (node (ref "ARD5V1") (pin "1") (pinfunction "1_1") (pintype "passive"))
      (node (ref "ARD5V1") (pin "11") (pinfunction "11_11") (pintype "passive"))
      (node (ref "ARD5V1") (pin "13") (pinfunction "13_13") (pintype "passive"))
      (node (ref "ARD5V1") (pin "15") (pinfunction "15_15") (pintype "passive"))
      (node (ref "ARD5V1") (pin "3") (pinfunction "3_3") (pintype "passive"))
      (node (ref "ARD5V1") (pin "5") (pinfunction "5_5") (pintype "passive"))
      (node (ref "ARD5V1") (pin "7") (pinfunction "7_7") (pintype "passive"))
      (node (ref "ARD5V1") (pin "9") (pinfunction "9_9") (pintype "passive"))
      (node (ref "ARD5V2") (pin "2") (pinfunction "2_2") (pintype "passive"))
      (node (ref "ARD5V2") (pin "3") (pinfunction "3_3") (pintype "passive"))
      (node (ref "ARD5V3") (pin "2") (pinfunction "2_2") (pintype "passive"))
      (node (ref "ARD5V3") (pin "3") (pinfunction "3_3") (pintype "passive"))
      (node (ref "ARD7") (pin "1") (pinfunction "1_1") (pintype "passive"))
      (node (ref "ARD8") (pin "1") (pinfunction "1_1") (pintype "passive"))
      (node (ref "DEMUX") (pin "7") (pinfunction "GND_7") (pintype "power_in"))
      (node (ref "HMI1") (pin "11") (pinfunction "11_11") (pintype "passive"))
      (node (ref "HMI1") (pin "2") (pinfunction "2_2") (pintype "passive"))
      (node (ref "LIM1") (pin "2") (pinfunction "2_2") (pintype "passive"))
      (node (ref "LIM2") (pin "2") (pinfunction "2_2") (pintype "passive"))
      (node (ref "LIM3") (pin "2") (pinfunction "2_2") (pintype "passive"))
      (node (ref "LIM4") (pin "2") (pinfunction "2_2") (pintype "passive"))
      (node (ref "LSH3V31") (pin "1") (pinfunction "1_1") (pintype "passive"))
      (node (ref "LSH3V32") (pin "1") (pinfunction "1_1") (pintype "passive"))
      (node (ref "LSH3V33") (pin "1") (pinfunction "1_1") (pintype "passive"))
      (node (ref "LSH5V1") (pin "1") (pinfunction "1_1") (pintype "passive"))
      (node (ref "LSH5V2") (pin "1") (pinfunction "1_1") (pintype "passive"))
      (node (ref "LSH5V3") (pin "1") (pinfunction "1_1") (pintype "passive"))
      (node (ref "LSHOUT1") (pin "1") (pinfunction "1_1") (pintype "passive"))
      (node (ref "LSHOUT2") (pin "1") (pinfunction "1_1") (pintype "passive"))
      (node (ref "LSHOUT3") (pin "1") (pinfunction "1_1") (pintype "passive"))
      (node (ref "MOSFETIN1") (pin "3") (pinfunction "3_3") (pintype "passive"))
      (node (ref "MOSFETIN1") (pin "4") (pinfunction "4_4") (pintype "passive"))
      (node (ref "MOSFETIN2") (pin "3") (pinfunction "3_3") (pintype "passive"))
      (node (ref "MOSFETIN2") (pin "4") (pinfunction "4_4") (pintype "passive"))
      (node (ref "MOSFETIN3") (pin "3") (pinfunction "3_3") (pintype "passive"))
      (node (ref "MOSFETIN3") (pin "4") (pinfunction "4_4") (pintype "passive"))
      (node (ref "MOSFETIN4") (pin "3") (pinfunction "3_3") (pintype "passive"))
      (node (ref "MOSFETIN4") (pin "4") (pinfunction "4_4") (pintype "passive"))
      (node (ref "MOSFETIN5") (pin "3") (pinfunction "3_3") (pintype "passive"))
      (node (ref "MOSFETIN5") (pin "4") (pinfunction "4_4") (pintype "passive"))
      (node (ref "MOSFETIN6") (pin "3") (pinfunction "3_3") (pintype "passive"))
      (node (ref "MOSFETIN6") (pin "4") (pinfunction "4_4") (pintype "passive"))
      (node (ref "MOSFETIN7") (pin "3") (pinfunction "3_3") (pintype "passive"))
      (node (ref "MOSFETIN7") (pin "4") (pinfunction "4_4") (pintype "passive"))
      (node (ref "MOSFETIN8") (pin "3") (pinfunction "3_3") (pintype "passive"))
      (node (ref "MOSFETIN8") (pin "4") (pinfunction "4_4") (pintype "passive"))
      (node (ref "PZTOUT1") (pin "2") (pinfunction "2_2") (pintype "passive"))
      (node (ref "PZTOUT2") (pin "P2") (pinfunction "2_P2") (pintype "passive"))
      (node (ref "RESET") (pin "3") (pinfunction "2_3") (pintype "passive"))
      (node (ref "SPI1") (pin "5") (pinfunction "5_5") (pintype "bidirectional"))
      (node (ref "STEPPERC1") (pin "2") (pinfunction "2_2") (pintype "passive"))
      (node (ref "STEPPERC2") (pin "2") (pinfunction "2_2") (pintype "passive"))
      (node (ref "STEPPERC3") (pin "2") (pinfunction "2_2") (pintype "passive"))
      (node (ref "STEPPERC4") (pin "2") (pinfunction "2_2") (pintype "passive"))
      (node (ref "STEPPERDRV1") (pin "1") (pinfunction "1_1") (pintype "passive"))
      (node (ref "STEPPERDRV1") (pin "7") (pinfunction "7_7") (pintype "passive"))
      (node (ref "STEPPERDRV2") (pin "1") (pinfunction "1_1") (pintype "passive"))
      (node (ref "STEPPERDRV2") (pin "7") (pinfunction "7_7") (pintype "passive"))
      (node (ref "STEPPERDRV3") (pin "1") (pinfunction "1_1") (pintype "passive"))
      (node (ref "STEPPERDRV3") (pin "7") (pinfunction "7_7") (pintype "passive"))
      (node (ref "STEPPERDRV4") (pin "1") (pinfunction "1_1") (pintype "passive"))
      (node (ref "STEPPERDRV4") (pin "7") (pinfunction "7_7") (pintype "passive"))
      (node (ref "U$1") (pin "5V_ICSP") (pinfunction "5V_ICSP_5V_ICSP") (pintype "bidirectional"))
      (node (ref "U$1") (pin "GND1") (pinfunction "GND1_GND1") (pintype "bidirectional"))
      (node (ref "U$1") (pin "GND_1") (pinfunction "GND_1_GND_1") (pintype "bidirectional"))
      (node (ref "U$1") (pin "GND_2") (pinfunction "GND_2_GND_2") (pintype "bidirectional"))
      (node (ref "U$1") (pin "GND_A") (pinfunction "GND_A_GND_A") (pintype "bidirectional"))
      (node (ref "U$1") (pin "GND_B") (pinfunction "GND_B_GND_B") (pintype "bidirectional"))
      (node (ref "U$1") (pin "GND_DEBUG") (pinfunction "GND_DEBUG_GND_DEBUG") (pintype "bidirectional"))
      (node (ref "VCCEXT1") (pin "P1") (pinfunction "1_P1") (pintype "passive"))
      (node (ref "VCCEXT2") (pin "P1") (pinfunction "1_P1") (pintype "passive"))
      (node (ref "VCCEXT3") (pin "P1") (pinfunction "1_P1") (pintype "passive"))
      (node (ref "VCCEXT4") (pin "P1") (pinfunction "1_P1") (pintype "passive"))
      (node (ref "VCCEXT5") (pin "P1") (pinfunction "1_P1") (pintype "passive"))
      (node (ref "VCCEXT6") (pin "P1") (pinfunction "1_P1") (pintype "passive"))
      (node (ref "VCCEXT7") (pin "P1") (pinfunction "1_P1") (pintype "passive"))
      (node (ref "VCCEXT8") (pin "P1") (pinfunction "1_P1") (pintype "passive"))
      (node (ref "VCCOUT1") (pin "2") (pinfunction "2_2") (pintype "passive"))
      (node (ref "VCCOUT1") (pin "3") (pinfunction "3_3") (pintype "passive"))
      (node (ref "VCCOUT2") (pin "2") (pinfunction "2_2") (pintype "passive"))
      (node (ref "VCCOUT2") (pin "3") (pinfunction "3_3") (pintype "passive"))
      (node (ref "VCCOUT3") (pin "2") (pinfunction "2_2") (pintype "passive"))
      (node (ref "VCCOUT3") (pin "3") (pinfunction "3_3") (pintype "passive"))
      (node (ref "VCCOUT4") (pin "2") (pinfunction "2_2") (pintype "passive"))
      (node (ref "VCCOUT4") (pin "3") (pinfunction "3_3") (pintype "passive"))
      (node (ref "VCCOUT5") (pin "2") (pinfunction "2_2") (pintype "passive"))
      (node (ref "VCCOUT5") (pin "3") (pinfunction "3_3") (pintype "passive"))
      (node (ref "VCCOUT6") (pin "2") (pinfunction "2_2") (pintype "passive"))
      (node (ref "VCCOUT6") (pin "3") (pinfunction "3_3") (pintype "passive"))
      (node (ref "VCCOUT7") (pin "2") (pinfunction "2_2") (pintype "passive"))
      (node (ref "VCCOUT7") (pin "3") (pinfunction "3_3") (pintype "passive"))
      (node (ref "VCCOUT8") (pin "2") (pinfunction "2_2") (pintype "passive"))
      (node (ref "VCCOUT8") (pin "3") (pinfunction "3_3") (pintype "passive"))
      (node (ref "VCCREG1") (pin "2") (pinfunction "2_2") (pintype "passive"))
      (node (ref "VCCREG2") (pin "2") (pinfunction "2_2") (pintype "passive"))
      (node (ref "VCCREG3") (pin "2") (pinfunction "2_2") (pintype "passive"))
      (node (ref "VCCREG4") (pin "2") (pinfunction "2_2") (pintype "passive"))
      (node (ref "VCCREG5") (pin "2") (pinfunction "2_2") (pintype "passive"))
      (node (ref "VCCREG6") (pin "2") (pinfunction "2_2") (pintype "passive"))
      (node (ref "VCCREG7") (pin "2") (pinfunction "2_2") (pintype "passive"))
      (node (ref "VCCREG8") (pin "2") (pinfunction "2_2") (pintype "passive"))
    )
    (net (code "93") (name "/IOREF") (class "Default")
      (node (ref "ARD1") (pin "2") (pinfunction "2_2") (pintype "passive"))
      (node (ref "U$1") (pin "IOREF") (pinfunction "IOREF_IOREF") (pintype "bidirectional"))
    )
    (net (code "94") (name "/MISO") (class "Default")
      (node (ref "SPI1") (pin "2") (pinfunction "2_2") (pintype "bidirectional"))
      (node (ref "U$1") (pin "MISO_ICSP") (pinfunction "MISO_ICSP_MISO_ICSP") (pintype "bidirectional"))
    )
    (net (code "95") (name "/MOSFETVCC1") (class "Default")
      (node (ref "MOSFETIN1") (pin "1") (pinfunction "1_1") (pintype "passive"))
      (node (ref "MOSFETIN1") (pin "2") (pinfunction "2_2") (pintype "passive"))
      (node (ref "MOSFETVCC1") (pin "2") (pinfunction "2_2") (pintype "passive"))
    )
    (net (code "96") (name "/MOSFETVCC2") (class "Default")
      (node (ref "MOSFETIN2") (pin "1") (pinfunction "1_1") (pintype "passive"))
      (node (ref "MOSFETIN2") (pin "2") (pinfunction "2_2") (pintype "passive"))
      (node (ref "MOSFETVCC2") (pin "2") (pinfunction "2_2") (pintype "passive"))
    )
    (net (code "97") (name "/MOSFETVCC3") (class "Default")
      (node (ref "MOSFETIN3") (pin "1") (pinfunction "1_1") (pintype "passive"))
      (node (ref "MOSFETIN3") (pin "2") (pinfunction "2_2") (pintype "passive"))
      (node (ref "MOSFETVCC3") (pin "2") (pinfunction "2_2") (pintype "passive"))
    )
    (net (code "98") (name "/MOSFETVCC4") (class "Default")
      (node (ref "MOSFETIN4") (pin "1") (pinfunction "1_1") (pintype "passive"))
      (node (ref "MOSFETIN4") (pin "2") (pinfunction "2_2") (pintype "passive"))
      (node (ref "MOSFETVCC4") (pin "2") (pinfunction "2_2") (pintype "passive"))
    )
    (net (code "99") (name "/MOSFETVCC5") (class "Default")
      (node (ref "MOSFETIN5") (pin "1") (pinfunction "1_1") (pintype "passive"))
      (node (ref "MOSFETIN5") (pin "2") (pinfunction "2_2") (pintype "passive"))
      (node (ref "MOSFETVCC5") (pin "2") (pinfunction "2_2") (pintype "passive"))
    )
    (net (code "100") (name "/MOSFETVCC6") (class "Default")
      (node (ref "MOSFETIN6") (pin "1") (pinfunction "1_1") (pintype "passive"))
      (node (ref "MOSFETIN6") (pin "2") (pinfunction "2_2") (pintype "passive"))
      (node (ref "MOSFETVCC6") (pin "2") (pinfunction "2_2") (pintype "passive"))
    )
    (net (code "101") (name "/MOSFETVCC7") (class "Default")
      (node (ref "MOSFETIN7") (pin "1") (pinfunction "1_1") (pintype "passive"))
      (node (ref "MOSFETIN7") (pin "2") (pinfunction "2_2") (pintype "passive"))
      (node (ref "MOSFETVCC7") (pin "2") (pinfunction "2_2") (pintype "passive"))
    )
    (net (code "102") (name "/MOSFETVCC8") (class "Default")
      (node (ref "MOSFETIN8") (pin "1") (pinfunction "1_1") (pintype "passive"))
      (node (ref "MOSFETIN8") (pin "2") (pinfunction "2_2") (pintype "passive"))
      (node (ref "MOSFETVCC8") (pin "2") (pinfunction "2_2") (pintype "passive"))
    )
    (net (code "103") (name "/MOSI") (class "Default")
      (node (ref "SPI1") (pin "3") (pinfunction "3_3") (pintype "bidirectional"))
      (node (ref "U$1") (pin "MOSI_ICSP") (pinfunction "MOSI_ICSP_MOSI_ICSP") (pintype "bidirectional"))
    )
    (net (code "104") (name "/REGVCC1") (class "Default")
      (node (ref "MOSFETVCC1") (pin "3") (pinfunction "3_3") (pintype "passive"))
      (node (ref "VCCOUT4") (pin "4") (pinfunction "4_4") (pintype "passive"))
      (node (ref "VCCOUT8") (pin "4") (pinfunction "4_4") (pintype "passive"))
      (node (ref "VCCREG1") (pin "1") (pinfunction "1_1") (pintype "passive"))
    )
    (net (code "105") (name "/REGVCC2") (class "Default")
      (node (ref "MOSFETVCC2") (pin "3") (pinfunction "3_3") (pintype "passive"))
      (node (ref "VCCOUT4") (pin "1") (pinfunction "1_1") (pintype "passive"))
      (node (ref "VCCOUT8") (pin "1") (pinfunction "1_1") (pintype "passive"))
      (node (ref "VCCREG2") (pin "1") (pinfunction "1_1") (pintype "passive"))
    )
    (net (code "106") (name "/REGVCC3") (class "Default")
      (node (ref "MOSFETVCC3") (pin "3") (pinfunction "3_3") (pintype "passive"))
      (node (ref "VCCOUT3") (pin "4") (pinfunction "4_4") (pintype "passive"))
      (node (ref "VCCOUT7") (pin "4") (pinfunction "4_4") (pintype "passive"))
      (node (ref "VCCREG3") (pin "1") (pinfunction "1_1") (pintype "passive"))
    )
    (net (code "107") (name "/REGVCC4") (class "Default")
      (node (ref "MOSFETVCC4") (pin "3") (pinfunction "3_3") (pintype "passive"))
      (node (ref "VCCOUT3") (pin "1") (pinfunction "1_1") (pintype "passive"))
      (node (ref "VCCOUT7") (pin "1") (pinfunction "1_1") (pintype "passive"))
      (node (ref "VCCREG4") (pin "1") (pinfunction "1_1") (pintype "passive"))
    )
    (net (code "108") (name "/REGVCC5") (class "Default")
      (node (ref "MOSFETVCC5") (pin "3") (pinfunction "3_3") (pintype "passive"))
      (node (ref "VCCOUT2") (pin "4") (pinfunction "4_4") (pintype "passive"))
      (node (ref "VCCOUT6") (pin "4") (pinfunction "4_4") (pintype "passive"))
      (node (ref "VCCREG5") (pin "1") (pinfunction "1_1") (pintype "passive"))
    )
    (net (code "109") (name "/REGVCC6") (class "Default")
      (node (ref "MOSFETVCC6") (pin "3") (pinfunction "3_3") (pintype "passive"))
      (node (ref "VCCOUT2") (pin "1") (pinfunction "1_1") (pintype "passive"))
      (node (ref "VCCOUT6") (pin "1") (pinfunction "1_1") (pintype "passive"))
      (node (ref "VCCREG6") (pin "1") (pinfunction "1_1") (pintype "passive"))
    )
    (net (code "110") (name "/REGVCC7") (class "Default")
      (node (ref "MOSFETVCC7") (pin "3") (pinfunction "3_3") (pintype "passive"))
      (node (ref "VCCOUT1") (pin "4") (pinfunction "4_4") (pintype "passive"))
      (node (ref "VCCOUT5") (pin "4") (pinfunction "4_4") (pintype "passive"))
      (node (ref "VCCREG7") (pin "1") (pinfunction "1_1") (pintype "passive"))
    )
    (net (code "111") (name "/REGVCC8") (class "Default")
      (node (ref "MOSFETVCC8") (pin "3") (pinfunction "3_3") (pintype "passive"))
      (node (ref "VCCOUT1") (pin "1") (pinfunction "1_1") (pintype "passive"))
      (node (ref "VCCOUT5") (pin "1") (pinfunction "1_1") (pintype "passive"))
      (node (ref "VCCREG8") (pin "1") (pinfunction "1_1") (pintype "passive"))
    )
    (net (code "112") (name "/RESET") (class "Default")
      (node (ref "ARD1") (pin "3") (pinfunction "3_3") (pintype "passive"))
      (node (ref "RESET") (pin "1") (pinfunction "1_1") (pintype "passive"))
      (node (ref "U$1") (pin "RESET") (pinfunction "RESET_RESET") (pintype "bidirectional"))
    )
    (net (code "113") (name "/RX0(D0)") (class "Default")
      (node (ref "ARD5") (pin "8") (pinfunction "8_8") (pintype "passive"))
      (node (ref "U$1") (pin "RX0") (pinfunction "RX0_RX0") (pintype "bidirectional"))
    )
    (net (code "114") (name "/RX1(19)") (class "Default")
      (node (ref "ARD6") (pin "6") (pinfunction "6_6") (pintype "passive"))
      (node (ref "DEMUX") (pin "10") (pinfunction "4B_10") (pintype "input"))
      (node (ref "DEMUX") (pin "2") (pinfunction "1B_2") (pintype "input"))
      (node (ref "DEMUX") (pin "3") (pinfunction "2B_3") (pintype "input"))
      (node (ref "DEMUX") (pin "9") (pinfunction "3B_9") (pintype "input"))
      (node (ref "U$1") (pin "RX1") (pinfunction "RX1_RX1") (pintype "bidirectional"))
      (node (ref "UARTR1") (pin "2") (pinfunction "2_2") (pintype "passive"))
    )
    (net (code "115") (name "/RX2(17)") (class "Default")
      (node (ref "ARD6") (pin "4") (pinfunction "4_4") (pintype "passive"))
      (node (ref "LSH3V31") (pin "3") (pinfunction "3_3") (pintype "passive"))
      (node (ref "U$1") (pin "RX2") (pinfunction "RX2_RX2") (pintype "bidirectional"))
    )
    (net (code "116") (name "/RX3(15)") (class "Default")
      (node (ref "ARD6") (pin "2") (pinfunction "2_2") (pintype "passive"))
      (node (ref "HMI1") (pin "16") (pinfunction "16_16") (pintype "passive"))
      (node (ref "U$1") (pin "RX3") (pinfunction "RX3_RX3") (pintype "bidirectional"))
    )
    (net (code "117") (name "/RX25V") (class "Default")
      (node (ref "LSH5V1") (pin "3") (pinfunction "3_3") (pintype "passive"))
      (node (ref "LSHOUT1") (pin "3") (pinfunction "3_3") (pintype "passive"))
    )
    (net (code "118") (name "/SCK") (class "Default")
      (node (ref "SPI1") (pin "4") (pinfunction "4_4") (pintype "bidirectional"))
      (node (ref "U$1") (pin "SCK_ICSP") (pinfunction "SCK_ICSP_SCK_ICSP") (pintype "bidirectional"))
    )
    (net (code "119") (name "/SCL(21)") (class "Default")
      (node (ref "ARD6") (pin "8") (pinfunction "8_8") (pintype "passive"))
      (node (ref "I2C3V3") (pin "1") (pinfunction "1_1") (pintype "passive"))
      (node (ref "I2C3V3") (pin "3") (pinfunction "3_3") (pintype "passive"))
      (node (ref "I2C3V3") (pin "5") (pinfunction "5_5") (pintype "passive"))
      (node (ref "I2C3V3") (pin "7") (pinfunction "7_7") (pintype "passive"))
      (node (ref "LSH3V31") (pin "5") (pinfunction "5_5") (pintype "passive"))
      (node (ref "U$1") (pin "SCL") (pinfunction "SCL_SCL") (pintype "bidirectional"))
    )
    (net (code "120") (name "/SCL1") (class "Default")
      (node (ref "ARD4") (pin "1") (pinfunction "1_1") (pintype "passive"))
      (node (ref "U$1") (pin "SCL1") (pinfunction "SCL1_SCL1") (pintype "bidirectional"))
    )
    (net (code "121") (name "/SCL5V") (class "Default")
      (node (ref "12DAC") (pin "4") (pinfunction "4_4") (pintype "passive"))
      (node (ref "16ADC") (pin "8") (pinfunction "8_8") (pintype "passive"))
      (node (ref "16ADCCONFIG") (pin "4") (pinfunction "4_4") (pintype "passive"))
      (node (ref "I2C5V") (pin "1") (pinfunction "1_1") (pintype "passive"))
      (node (ref "I2C5V") (pin "3") (pinfunction "3_3") (pintype "passive"))
      (node (ref "I2C5V") (pin "5") (pinfunction "5_5") (pintype "passive"))
      (node (ref "I2C5V") (pin "7") (pinfunction "7_7") (pintype "passive"))
      (node (ref "LSH5V1") (pin "5") (pinfunction "5_5") (pintype "passive"))
      (node (ref "LSHOUT1") (pin "5") (pinfunction "5_5") (pintype "passive"))
    )
    (net (code "122") (name "/SDA(20)") (class "Default")
      (node (ref "ARD6") (pin "7") (pinfunction "7_7") (pintype "passive"))
      (node (ref "I2C3V3") (pin "2") (pinfunction "2_2") (pintype "passive"))
      (node (ref "I2C3V3") (pin "4") (pinfunction "4_4") (pintype "passive"))
      (node (ref "I2C3V3") (pin "6") (pinfunction "6_6") (pintype "passive"))
      (node (ref "I2C3V3") (pin "8") (pinfunction "8_8") (pintype "passive"))
      (node (ref "LSH3V31") (pin "4") (pinfunction "4_4") (pintype "passive"))
      (node (ref "U$1") (pin "SDA") (pinfunction "SDA_SDA") (pintype "bidirectional"))
    )
    (net (code "123") (name "/SDA1") (class "Default")
      (node (ref "ARD4") (pin "2") (pinfunction "2_2") (pintype "passive"))
      (node (ref "U$1") (pin "SDA1") (pinfunction "SDA1_SDA1") (pintype "bidirectional"))
    )
    (net (code "124") (name "/SDA5V") (class "Default")
      (node (ref "12DAC") (pin "3") (pinfunction "3_3") (pintype "passive"))
      (node (ref "16ADC") (pin "7") (pinfunction "7_7") (pintype "passive"))
      (node (ref "16ADCCONFIG") (pin "3") (pinfunction "3_3") (pintype "passive"))
      (node (ref "I2C5V") (pin "2") (pinfunction "2_2") (pintype "passive"))
      (node (ref "I2C5V") (pin "4") (pinfunction "4_4") (pintype "passive"))
      (node (ref "I2C5V") (pin "6") (pinfunction "6_6") (pintype "passive"))
      (node (ref "I2C5V") (pin "8") (pinfunction "8_8") (pintype "passive"))
      (node (ref "LSH5V1") (pin "4") (pinfunction "4_4") (pintype "passive"))
      (node (ref "LSHOUT1") (pin "4") (pinfunction "4_4") (pintype "passive"))
    )
    (net (code "125") (name "/SPIRESET") (class "Default")
      (node (ref "SPI1") (pin "6") (pinfunction "6_6") (pintype "bidirectional"))
      (node (ref "U$1") (pin "RESET_ICSP") (pinfunction "RESET_ICSP_RESET_ICSP") (pintype "bidirectional"))
    )
    (net (code "126") (name "/STEPM1A1") (class "Default")
      (node (ref "STEPPERDRV1") (pin "4") (pinfunction "4_4") (pintype "passive"))
      (node (ref "STEPPEROUT1") (pin "2") (pinfunction "2_2") (pintype "passive"))
    )
    (net (code "127") (name "/STEPM1A2") (class "Default")
      (node (ref "STEPPERDRV2") (pin "4") (pinfunction "4_4") (pintype "passive"))
      (node (ref "STEPPEROUT2") (pin "2") (pinfunction "2_2") (pintype "passive"))
    )
    (net (code "128") (name "/STEPM1A3") (class "Default")
      (node (ref "STEPPERDRV3") (pin "4") (pinfunction "4_4") (pintype "passive"))
      (node (ref "STEPPEROUT3") (pin "2") (pinfunction "2_2") (pintype "passive"))
    )
    (net (code "129") (name "/STEPM1A4") (class "Default")
      (node (ref "STEPPERDRV4") (pin "4") (pinfunction "4_4") (pintype "passive"))
      (node (ref "STEPPEROUT4") (pin "2") (pinfunction "2_2") (pintype "passive"))
    )
    (net (code "130") (name "/STEPM1B1") (class "Default")
      (node (ref "STEPPERDRV1") (pin "3") (pinfunction "3_3") (pintype "passive"))
      (node (ref "STEPPEROUT1") (pin "1") (pinfunction "1_1") (pintype "passive"))
    )
    (net (code "131") (name "/STEPM1B2") (class "Default")
      (node (ref "STEPPERDRV2") (pin "3") (pinfunction "3_3") (pintype "passive"))
      (node (ref "STEPPEROUT2") (pin "1") (pinfunction "1_1") (pintype "passive"))
    )
    (net (code "132") (name "/STEPM1B3") (class "Default")
      (node (ref "STEPPERDRV3") (pin "3") (pinfunction "3_3") (pintype "passive"))
      (node (ref "STEPPEROUT3") (pin "1") (pinfunction "1_1") (pintype "passive"))
    )
    (net (code "133") (name "/STEPM1B4") (class "Default")
      (node (ref "STEPPERDRV4") (pin "3") (pinfunction "3_3") (pintype "passive"))
      (node (ref "STEPPEROUT4") (pin "1") (pinfunction "1_1") (pintype "passive"))
    )
    (net (code "134") (name "/STEPM2A1") (class "Default")
      (node (ref "STEPPERDRV1") (pin "5") (pinfunction "5_5") (pintype "passive"))
      (node (ref "STEPPEROUT1") (pin "3") (pinfunction "3_3") (pintype "passive"))
    )
    (net (code "135") (name "/STEPM2A2") (class "Default")
      (node (ref "STEPPERDRV2") (pin "5") (pinfunction "5_5") (pintype "passive"))
      (node (ref "STEPPEROUT2") (pin "3") (pinfunction "3_3") (pintype "passive"))
    )
    (net (code "136") (name "/STEPM2A3") (class "Default")
      (node (ref "STEPPERDRV3") (pin "5") (pinfunction "5_5") (pintype "passive"))
      (node (ref "STEPPEROUT3") (pin "3") (pinfunction "3_3") (pintype "passive"))
    )
    (net (code "137") (name "/STEPM2A4") (class "Default")
      (node (ref "STEPPERDRV4") (pin "5") (pinfunction "5_5") (pintype "passive"))
      (node (ref "STEPPEROUT4") (pin "3") (pinfunction "3_3") (pintype "passive"))
    )
    (net (code "138") (name "/STEPM2B1") (class "Default")
      (node (ref "STEPPERDRV1") (pin "6") (pinfunction "6_6") (pintype "passive"))
      (node (ref "STEPPEROUT1") (pin "4") (pinfunction "4_4") (pintype "passive"))
    )
    (net (code "139") (name "/STEPM2B2") (class "Default")
      (node (ref "STEPPERDRV2") (pin "6") (pinfunction "6_6") (pintype "passive"))
      (node (ref "STEPPEROUT2") (pin "4") (pinfunction "4_4") (pintype "passive"))
    )
    (net (code "140") (name "/STEPM2B3") (class "Default")
      (node (ref "STEPPERDRV3") (pin "6") (pinfunction "6_6") (pintype "passive"))
      (node (ref "STEPPEROUT3") (pin "4") (pinfunction "4_4") (pintype "passive"))
    )
    (net (code "141") (name "/STEPM2B4") (class "Default")
      (node (ref "STEPPERDRV4") (pin "6") (pinfunction "6_6") (pintype "passive"))
      (node (ref "STEPPEROUT4") (pin "4") (pinfunction "4_4") (pintype "passive"))
    )
    (net (code "142") (name "/STEPUART1") (class "Default")
      (node (ref "DEMUX") (pin "11") (pinfunction "4A_11") (pintype "input"))
      (node (ref "STEPPERIN1") (pin "3") (pinfunction "3_3") (pintype "passive"))
    )
    (net (code "143") (name "/STEPUART2") (class "Default")
      (node (ref "DEMUX") (pin "8") (pinfunction "3A_8") (pintype "input"))
      (node (ref "STEPPERIN2") (pin "3") (pinfunction "3_3") (pintype "passive"))
    )
    (net (code "144") (name "/STEPUART3") (class "Default")
      (node (ref "DEMUX") (pin "1") (pinfunction "1A_1") (pintype "input"))
      (node (ref "STEPPERIN3") (pin "3") (pinfunction "3_3") (pintype "passive"))
    )
    (net (code "145") (name "/STEPUART4") (class "Default")
      (node (ref "DEMUX") (pin "4") (pinfunction "2A_4") (pintype "input"))
      (node (ref "STEPPERIN4") (pin "3") (pinfunction "3_3") (pintype "passive"))
    )
    (net (code "146") (name "/TX0(D1)") (class "Default")
      (node (ref "ARD5") (pin "7") (pinfunction "7_7") (pintype "passive"))
      (node (ref "U$1") (pin "TX0") (pinfunction "TX0_TX0") (pintype "bidirectional"))
    )
    (net (code "147") (name "/TX1(18)") (class "Default")
      (node (ref "ARD6") (pin "5") (pinfunction "5_5") (pintype "passive"))
      (node (ref "U$1") (pin "TX1") (pinfunction "TX1_TX1") (pintype "bidirectional"))
      (node (ref "UARTR1") (pin "1") (pinfunction "1_1") (pintype "passive"))
    )
    (net (code "148") (name "/TX2(16)") (class "Default")
      (node (ref "ARD6") (pin "3") (pinfunction "3_3") (pintype "passive"))
      (node (ref "LSH3V31") (pin "2") (pinfunction "2_2") (pintype "passive"))
      (node (ref "U$1") (pin "TX2") (pinfunction "TX2_TX2") (pintype "bidirectional"))
    )
    (net (code "149") (name "/TX3(14)") (class "Default")
      (node (ref "ARD6") (pin "1") (pinfunction "1_1") (pintype "passive"))
      (node (ref "HMI1") (pin "14") (pinfunction "14_14") (pintype "passive"))
      (node (ref "U$1") (pin "TX3") (pinfunction "TX3_TX3") (pintype "bidirectional"))
    )
    (net (code "150") (name "/TX25V") (class "Default")
      (node (ref "LSH5V1") (pin "2") (pinfunction "2_2") (pintype "passive"))
      (node (ref "LSHOUT1") (pin "2") (pinfunction "2_2") (pintype "passive"))
    )
    (net (code "151") (name "/VIN") (class "Default")
      (node (ref "ARD1") (pin "8") (pinfunction "8_8") (pintype "passive"))
      (node (ref "U$1") (pin "VIN") (pinfunction "VIN_VIN") (pintype "bidirectional"))
    )
    (net (code "152") (name "unconnected-(12VIN-Pad2)") (class "Default")
      (node (ref "12VIN") (pin "2") (pinfunction "2_2") (pintype "passive"))
    )
    (net (code "153") (name "unconnected-(ARD1-Pad1)") (class "Default")
      (node (ref "ARD1") (pin "1") (pinfunction "1_1") (pintype "passive"))
    )
    (net (code "154") (name "unconnected-(STEPPERIN1-Pad4)") (class "Default")
      (node (ref "STEPPERIN1") (pin "4") (pinfunction "4_4") (pintype "passive"))
    )
    (net (code "155") (name "unconnected-(STEPPERIN1-Pad5)") (class "Default")
      (node (ref "STEPPERIN1") (pin "5") (pinfunction "5_5") (pintype "passive"))
    )
    (net (code "156") (name "unconnected-(STEPPERIN1-Pad6)") (class "Default")
      (node (ref "STEPPERIN1") (pin "6") (pinfunction "6_6") (pintype "passive"))
    )
    (net (code "157") (name "unconnected-(STEPPERIN1-Pad7)") (class "Default")
      (node (ref "STEPPERIN1") (pin "7") (pinfunction "7_7") (pintype "passive"))
    )
    (net (code "158") (name "unconnected-(STEPPERIN1-Pad8)") (class "Default")
      (node (ref "STEPPERIN1") (pin "8") (pinfunction "8_8") (pintype "passive"))
    )
    (net (code "159") (name "unconnected-(STEPPERIN2-Pad4)") (class "Default")
      (node (ref "STEPPERIN2") (pin "4") (pinfunction "4_4") (pintype "passive"))
    )
    (net (code "160") (name "unconnected-(STEPPERIN2-Pad5)") (class "Default")
      (node (ref "STEPPERIN2") (pin "5") (pinfunction "5_5") (pintype "passive"))
    )
    (net (code "161") (name "unconnected-(STEPPERIN2-Pad6)") (class "Default")
      (node (ref "STEPPERIN2") (pin "6") (pinfunction "6_6") (pintype "passive"))
    )
    (net (code "162") (name "unconnected-(STEPPERIN2-Pad7)") (class "Default")
      (node (ref "STEPPERIN2") (pin "7") (pinfunction "7_7") (pintype "passive"))
    )
    (net (code "163") (name "unconnected-(STEPPERIN2-Pad8)") (class "Default")
      (node (ref "STEPPERIN2") (pin "8") (pinfunction "8_8") (pintype "passive"))
    )
    (net (code "164") (name "unconnected-(STEPPERIN3-Pad4)") (class "Default")
      (node (ref "STEPPERIN3") (pin "4") (pinfunction "4_4") (pintype "passive"))
    )
    (net (code "165") (name "unconnected-(STEPPERIN3-Pad5)") (class "Default")
      (node (ref "STEPPERIN3") (pin "5") (pinfunction "5_5") (pintype "passive"))
    )
    (net (code "166") (name "unconnected-(STEPPERIN3-Pad6)") (class "Default")
      (node (ref "STEPPERIN3") (pin "6") (pinfunction "6_6") (pintype "passive"))
    )
    (net (code "167") (name "unconnected-(STEPPERIN3-Pad7)") (class "Default")
      (node (ref "STEPPERIN3") (pin "7") (pinfunction "7_7") (pintype "passive"))
    )
    (net (code "168") (name "unconnected-(STEPPERIN3-Pad8)") (class "Default")
      (node (ref "STEPPERIN3") (pin "8") (pinfunction "8_8") (pintype "passive"))
    )
    (net (code "169") (name "unconnected-(STEPPERIN4-Pad4)") (class "Default")
      (node (ref "STEPPERIN4") (pin "4") (pinfunction "4_4") (pintype "passive"))
    )
    (net (code "170") (name "unconnected-(STEPPERIN4-Pad5)") (class "Default")
      (node (ref "STEPPERIN4") (pin "5") (pinfunction "5_5") (pintype "passive"))
    )
    (net (code "171") (name "unconnected-(STEPPERIN4-Pad6)") (class "Default")
      (node (ref "STEPPERIN4") (pin "6") (pinfunction "6_6") (pintype "passive"))
    )
    (net (code "172") (name "unconnected-(STEPPERIN4-Pad7)") (class "Default")
      (node (ref "STEPPERIN4") (pin "7") (pinfunction "7_7") (pintype "passive"))
    )
    (net (code "173") (name "unconnected-(STEPPERIN4-Pad8)") (class "Default")
      (node (ref "STEPPERIN4") (pin "8") (pinfunction "8_8") (pintype "passive"))
    )
    (net (code "174") (name "unconnected-(U$1-PadNC)") (class "Default")
      (node (ref "U$1") (pin "NC") (pinfunction "NC_NC") (pintype "bidirectional"))
    )
    (net (code "175") (name "unconnected-(VCCREG1-Pad4)") (class "Default")
      (node (ref "VCCREG1") (pin "4") (pinfunction "4_4") (pintype "passive"))
    )
    (net (code "176") (name "unconnected-(VCCREG1-Pad5)") (class "Default")
      (node (ref "VCCREG1") (pin "5") (pinfunction "5_5") (pintype "passive"))
    )
    (net (code "177") (name "unconnected-(VCCREG2-Pad4)") (class "Default")
      (node (ref "VCCREG2") (pin "4") (pinfunction "4_4") (pintype "passive"))
    )
    (net (code "178") (name "unconnected-(VCCREG2-Pad5)") (class "Default")
      (node (ref "VCCREG2") (pin "5") (pinfunction "5_5") (pintype "passive"))
    )
    (net (code "179") (name "unconnected-(VCCREG3-Pad4)") (class "Default")
      (node (ref "VCCREG3") (pin "4") (pinfunction "4_4") (pintype "passive"))
    )
    (net (code "180") (name "unconnected-(VCCREG3-Pad5)") (class "Default")
      (node (ref "VCCREG3") (pin "5") (pinfunction "5_5") (pintype "passive"))
    )
    (net (code "181") (name "unconnected-(VCCREG4-Pad4)") (class "Default")
      (node (ref "VCCREG4") (pin "4") (pinfunction "4_4") (pintype "passive"))
    )
    (net (code "182") (name "unconnected-(VCCREG4-Pad5)") (class "Default")
      (node (ref "VCCREG4") (pin "5") (pinfunction "5_5") (pintype "passive"))
    )
    (net (code "183") (name "unconnected-(VCCREG5-Pad4)") (class "Default")
      (node (ref "VCCREG5") (pin "4") (pinfunction "4_4") (pintype "passive"))
    )
    (net (code "184") (name "unconnected-(VCCREG5-Pad5)") (class "Default")
      (node (ref "VCCREG5") (pin "5") (pinfunction "5_5") (pintype "passive"))
    )
    (net (code "185") (name "unconnected-(VCCREG6-Pad4)") (class "Default")
      (node (ref "VCCREG6") (pin "4") (pinfunction "4_4") (pintype "passive"))
    )
    (net (code "186") (name "unconnected-(VCCREG6-Pad5)") (class "Default")
      (node (ref "VCCREG6") (pin "5") (pinfunction "5_5") (pintype "passive"))
    )
    (net (code "187") (name "unconnected-(VCCREG7-Pad4)") (class "Default")
      (node (ref "VCCREG7") (pin "4") (pinfunction "4_4") (pintype "passive"))
    )
    (net (code "188") (name "unconnected-(VCCREG7-Pad5)") (class "Default")
      (node (ref "VCCREG7") (pin "5") (pinfunction "5_5") (pintype "passive"))
    )
    (net (code "189") (name "unconnected-(VCCREG8-Pad4)") (class "Default")
      (node (ref "VCCREG8") (pin "4") (pinfunction "4_4") (pintype "passive"))
    )
    (net (code "190") (name "unconnected-(VCCREG8-Pad5)") (class "Default")
      (node (ref "VCCREG8") (pin "5") (pinfunction "5_5") (pintype "passive"))
    )
  )
)
